# Rover_PCB_2019-02-01.net
KiCad netlist of a schematic drawn in EAGLE
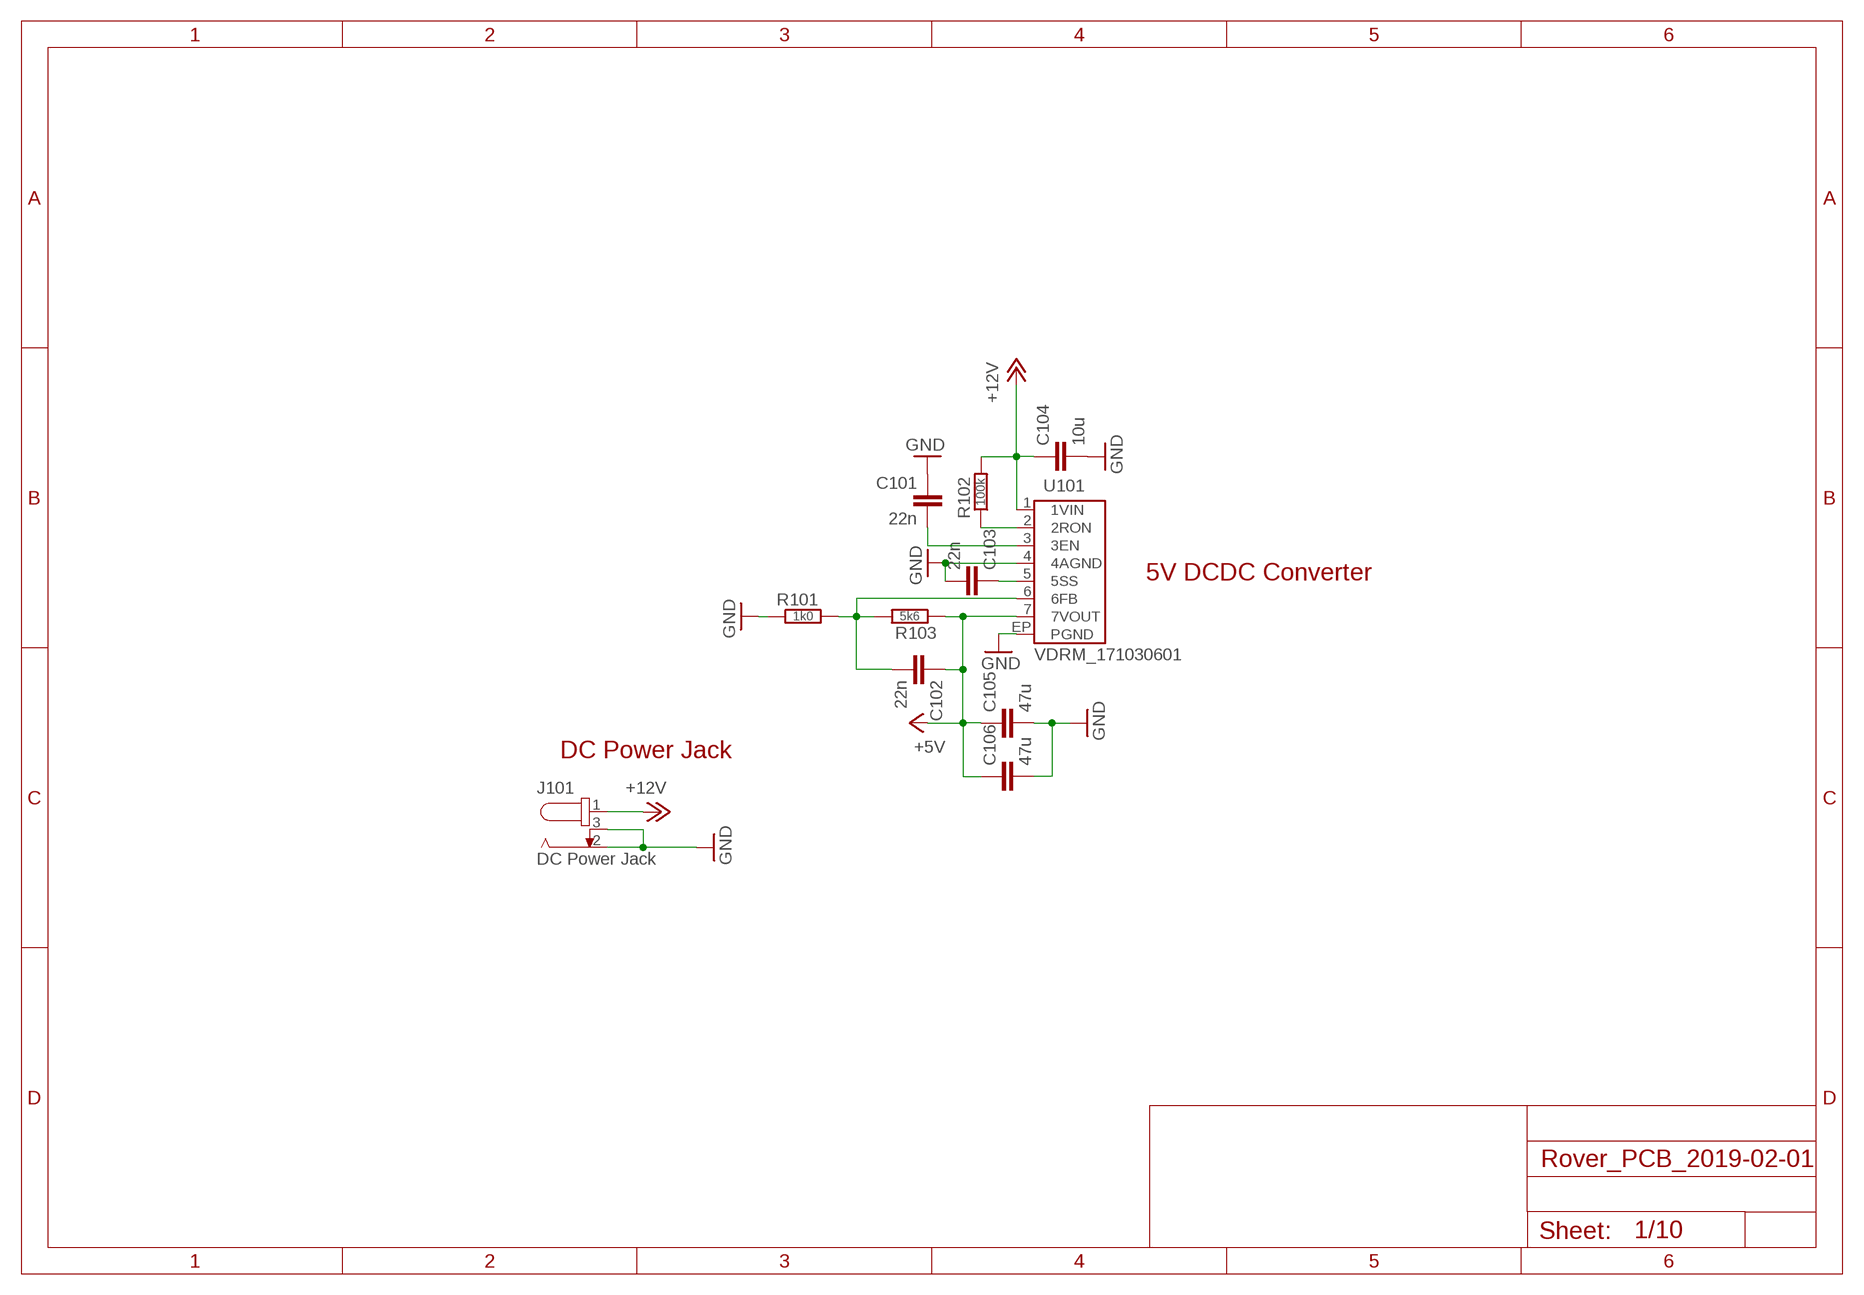
[diagram p0: schematic, sheet 1]
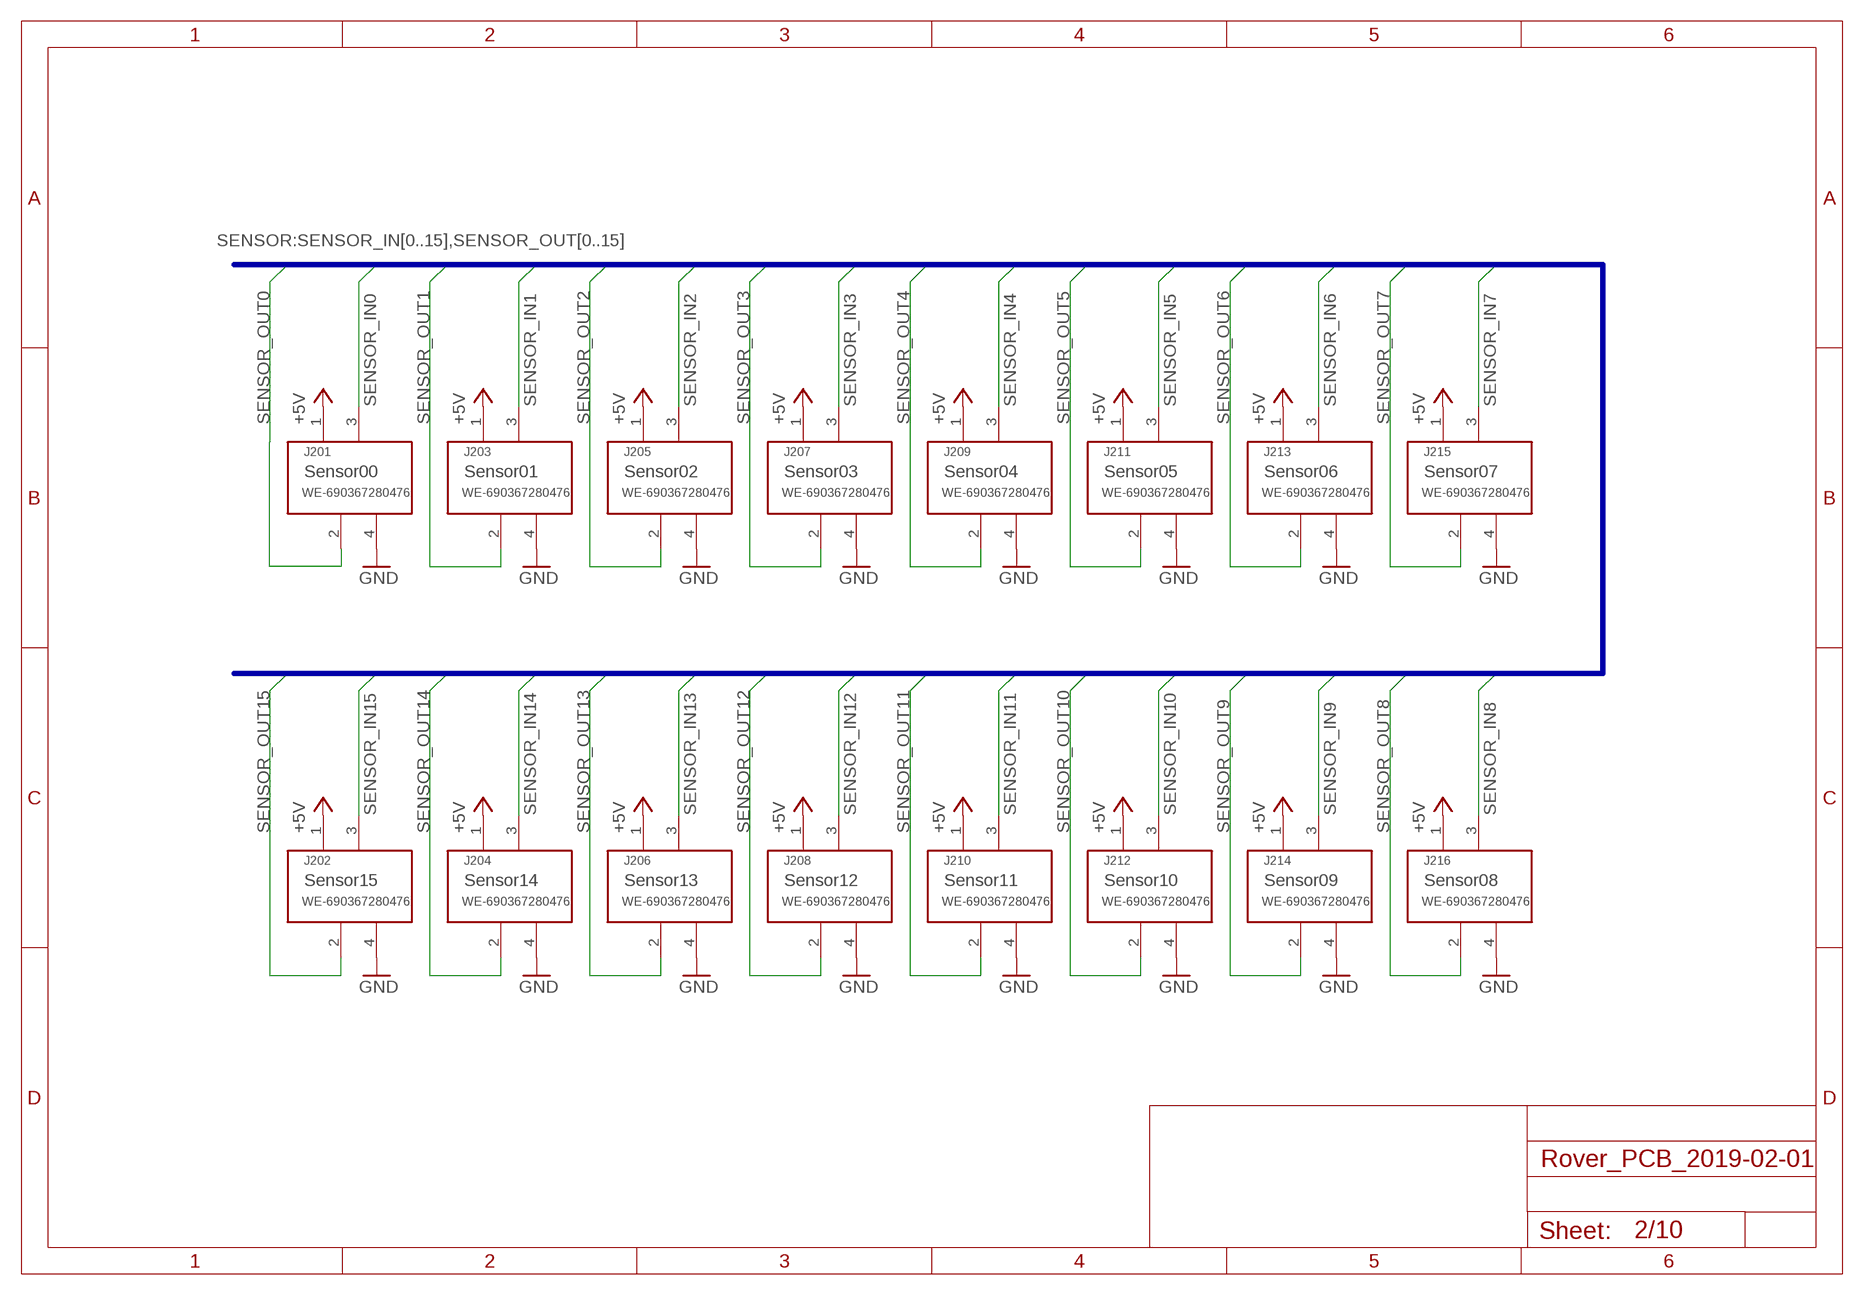
[diagram p1: schematic, sheet 2]
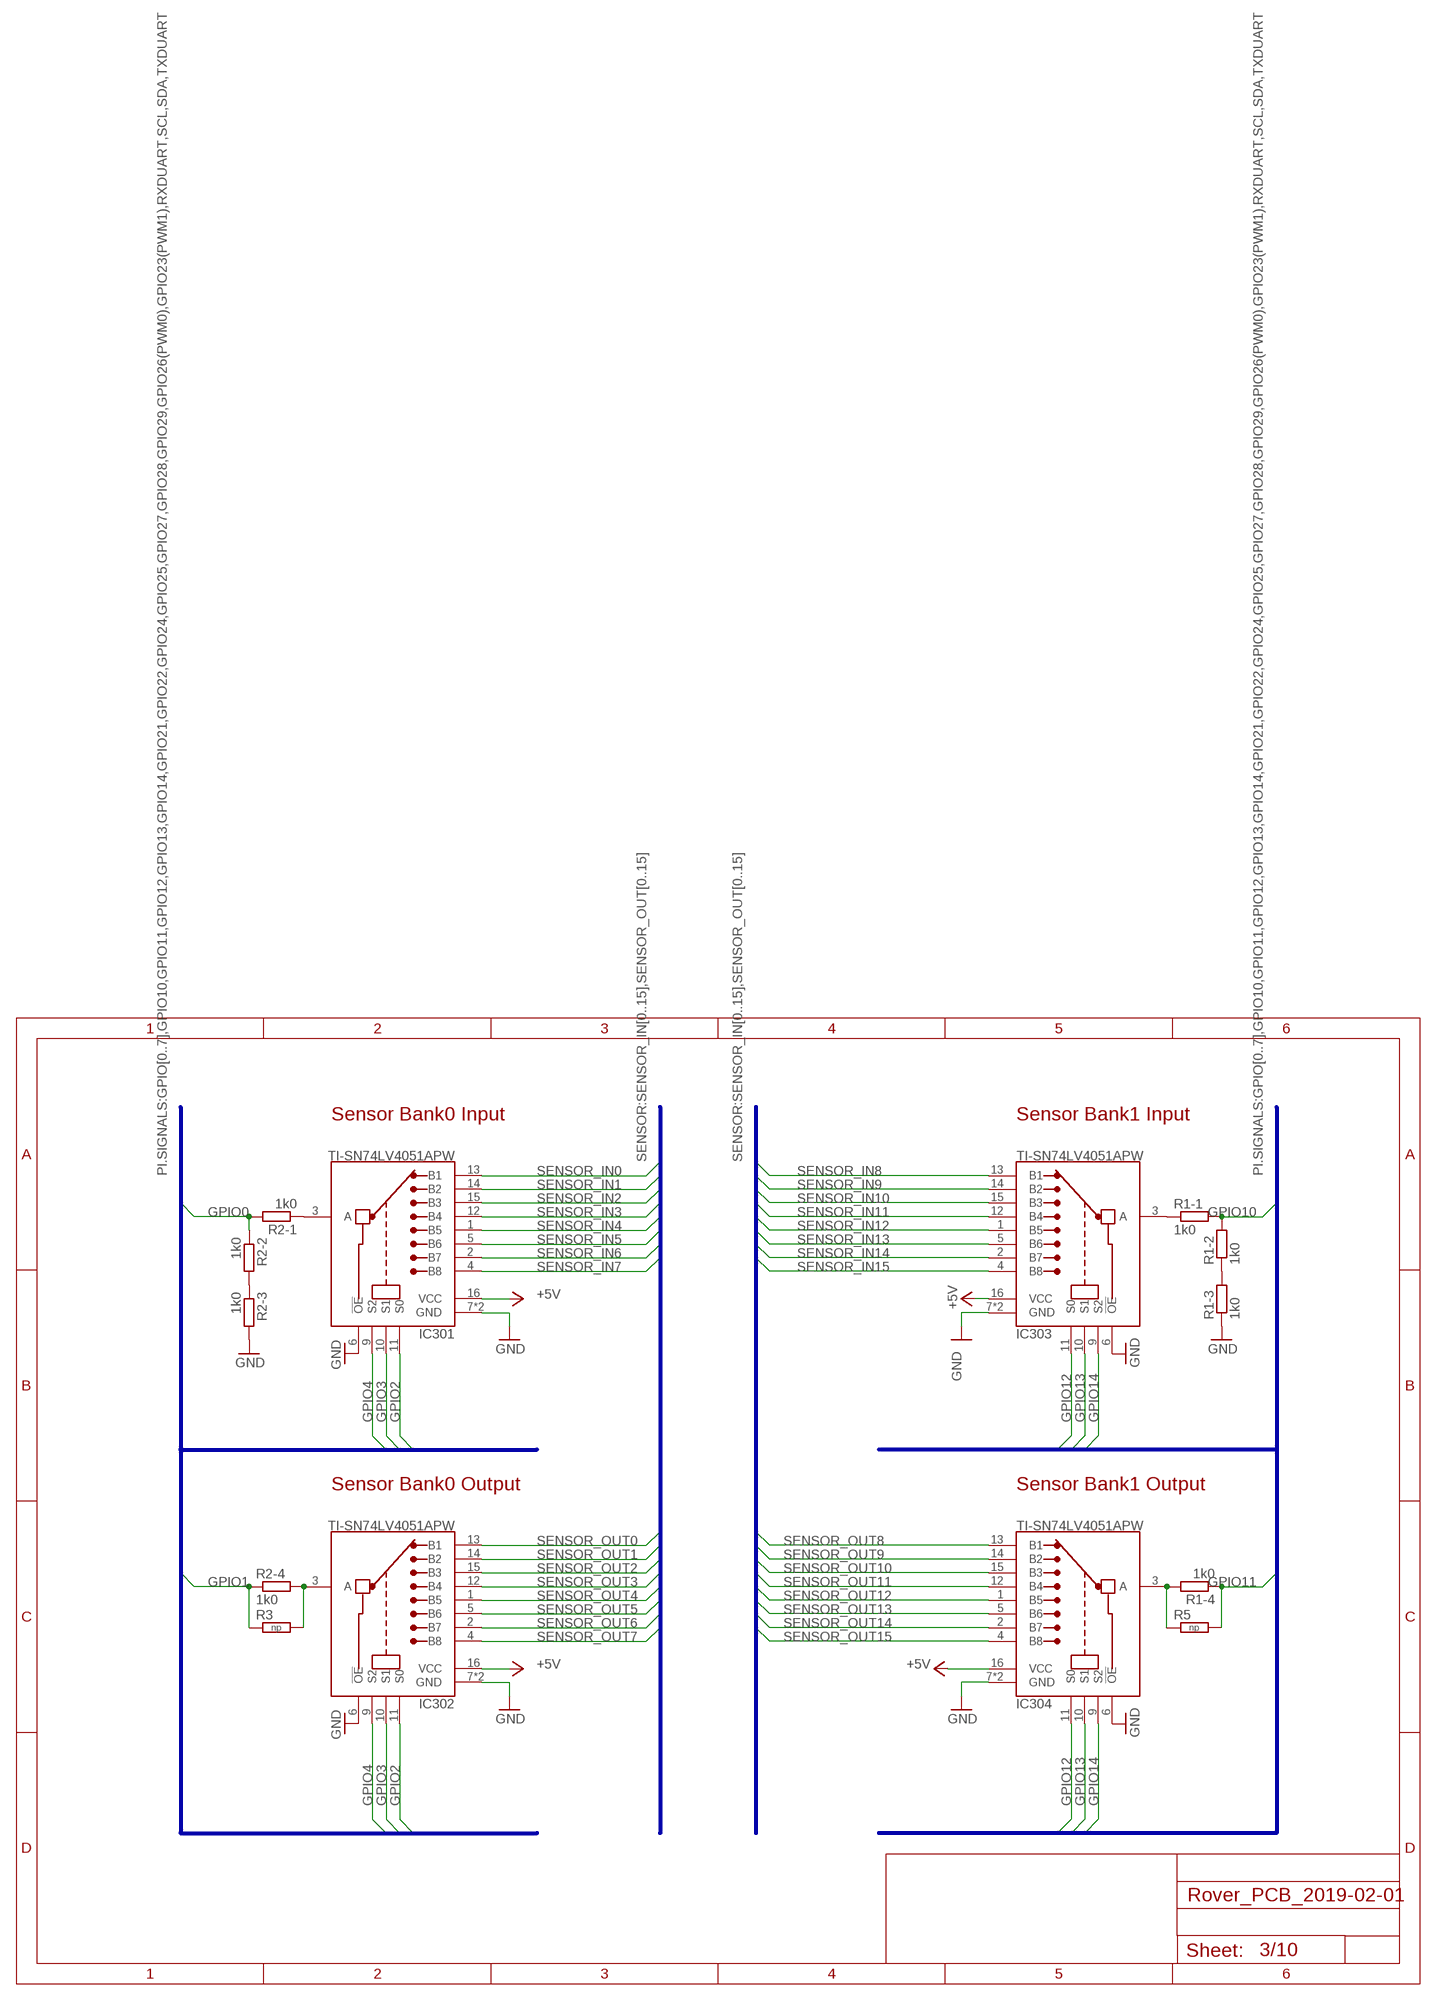
[diagram p2: schematic, sheet 3]
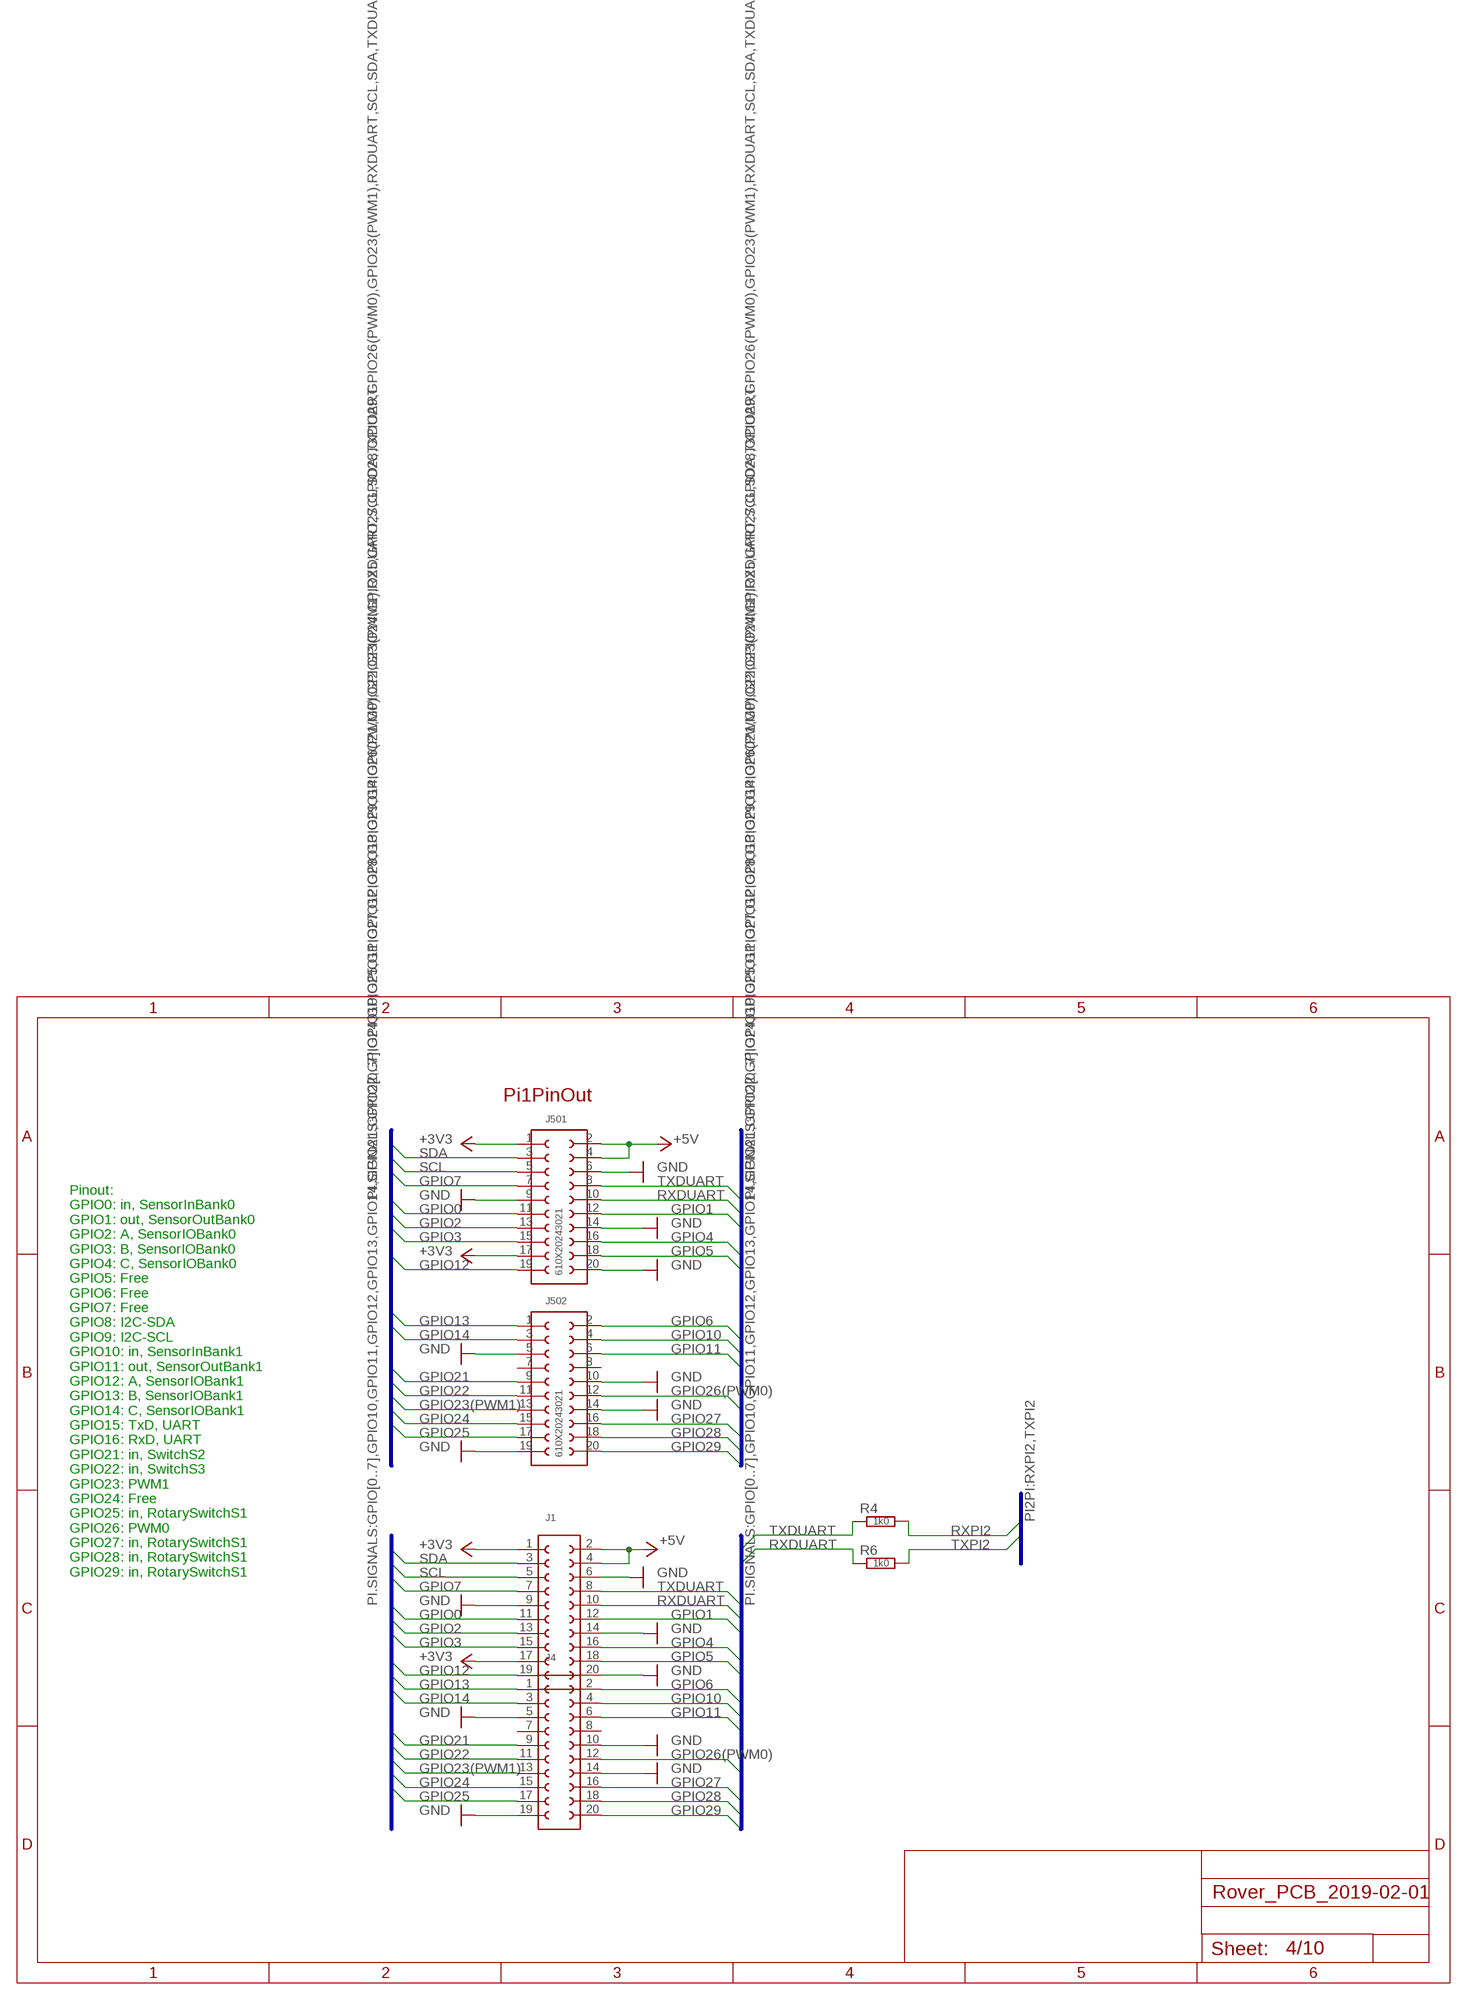
[diagram p3: schematic, sheet 4]
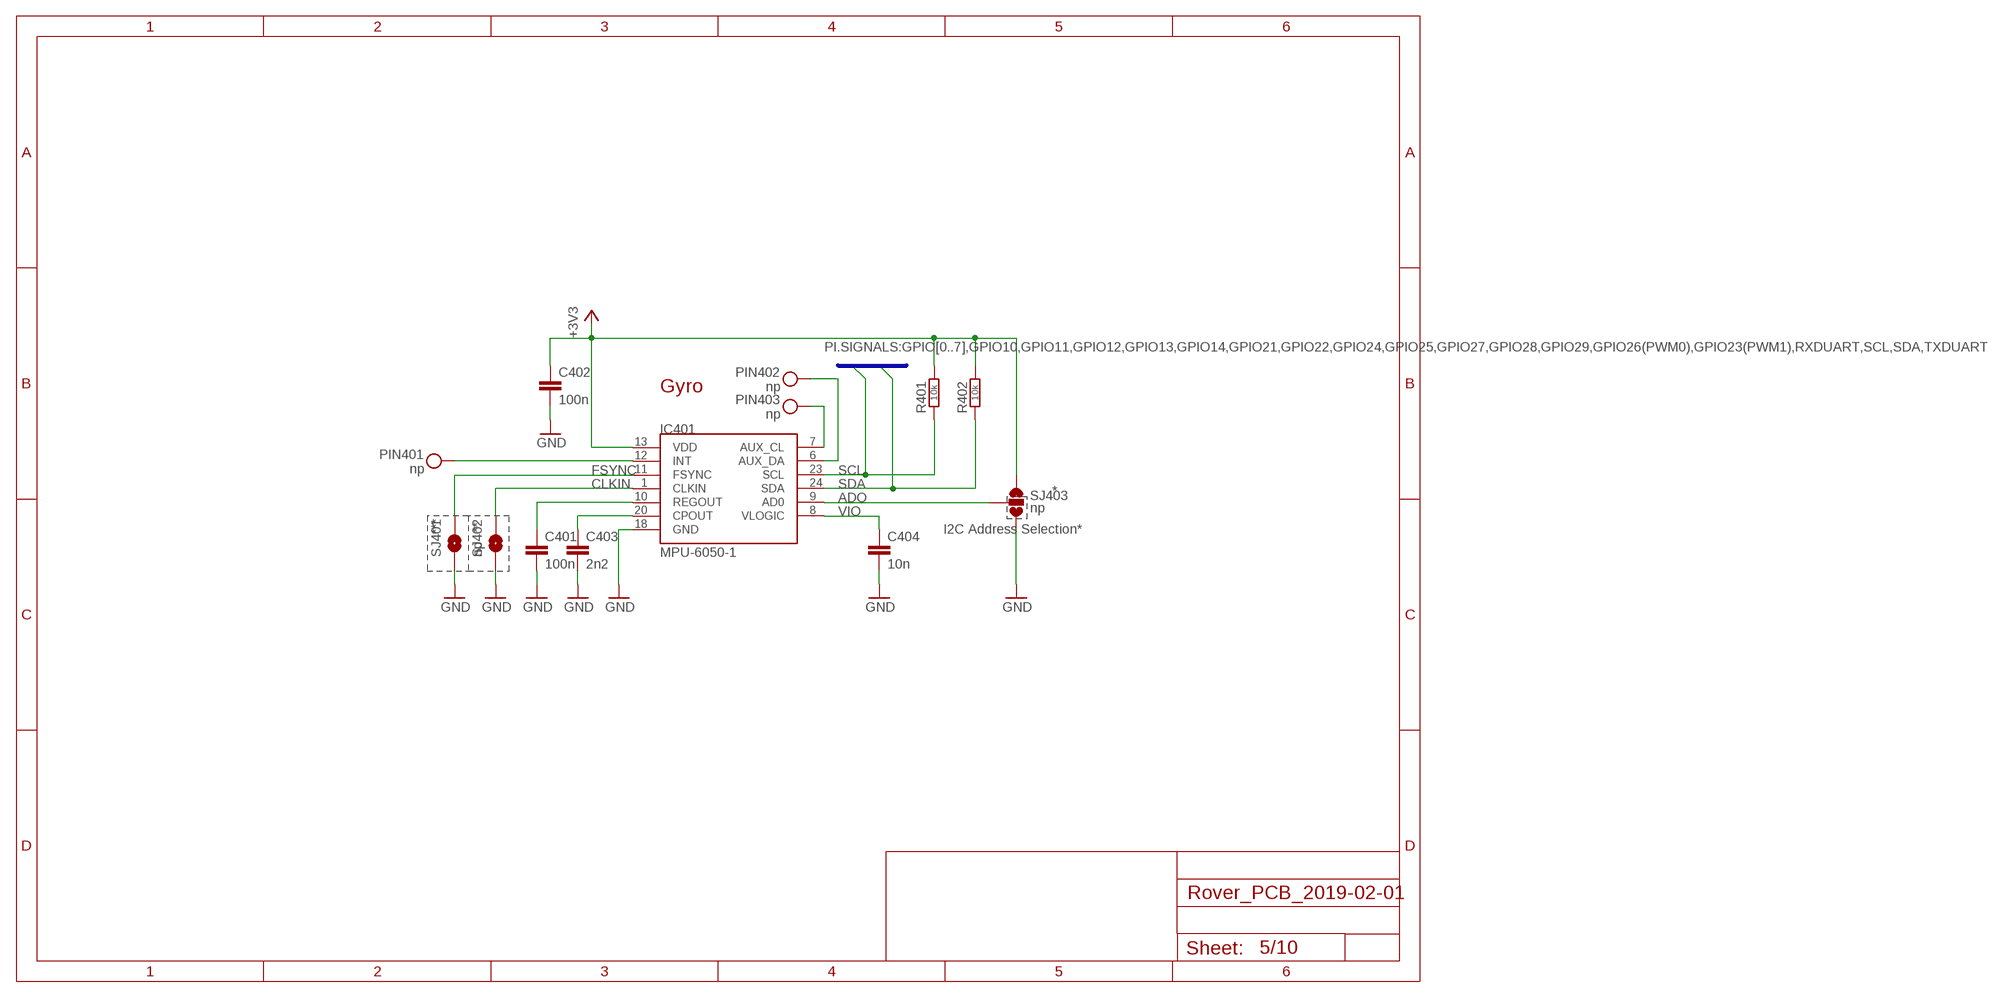
[diagram p4: schematic, sheet 5]
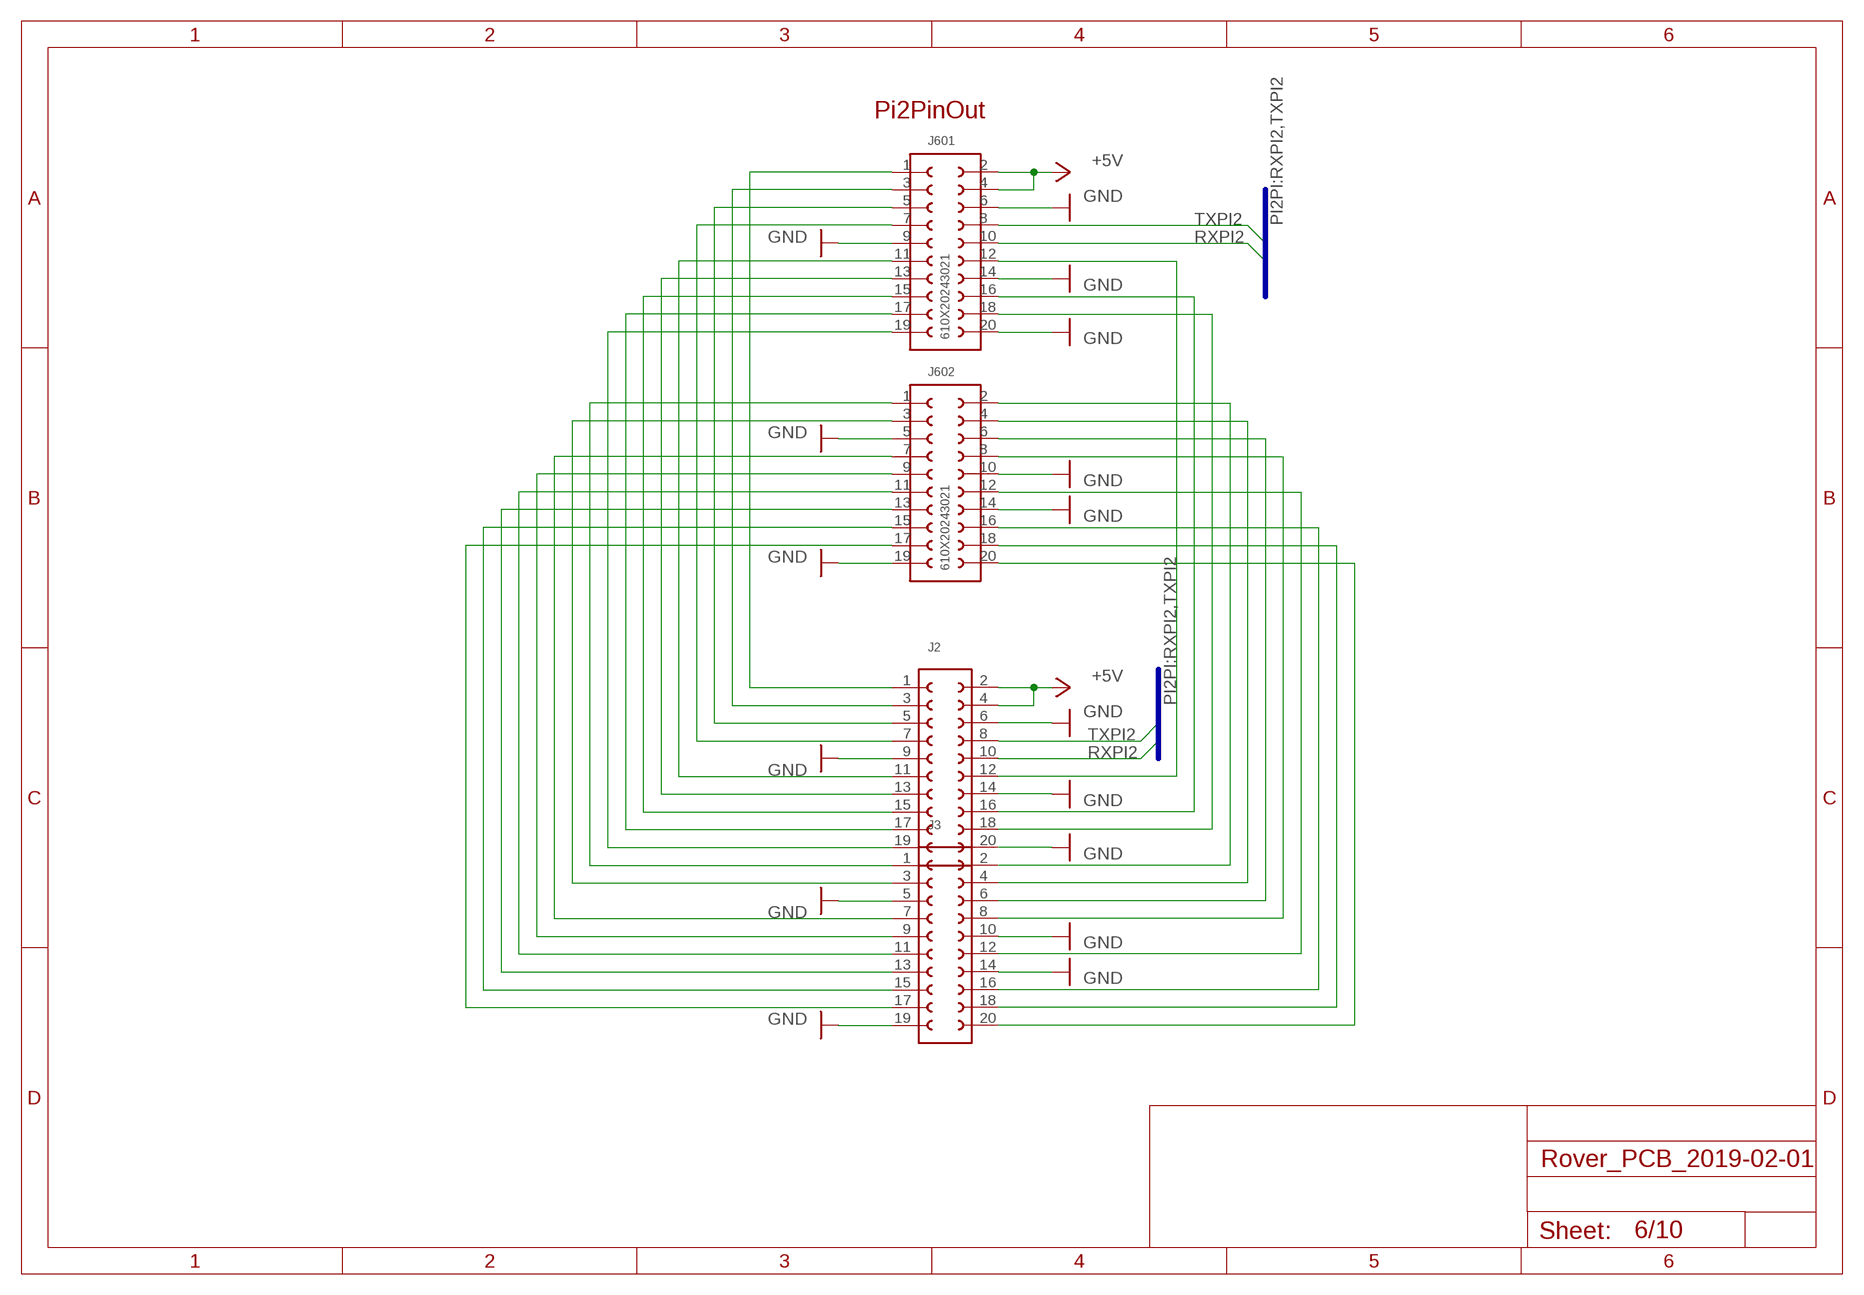
[diagram p5: schematic, sheet 6]
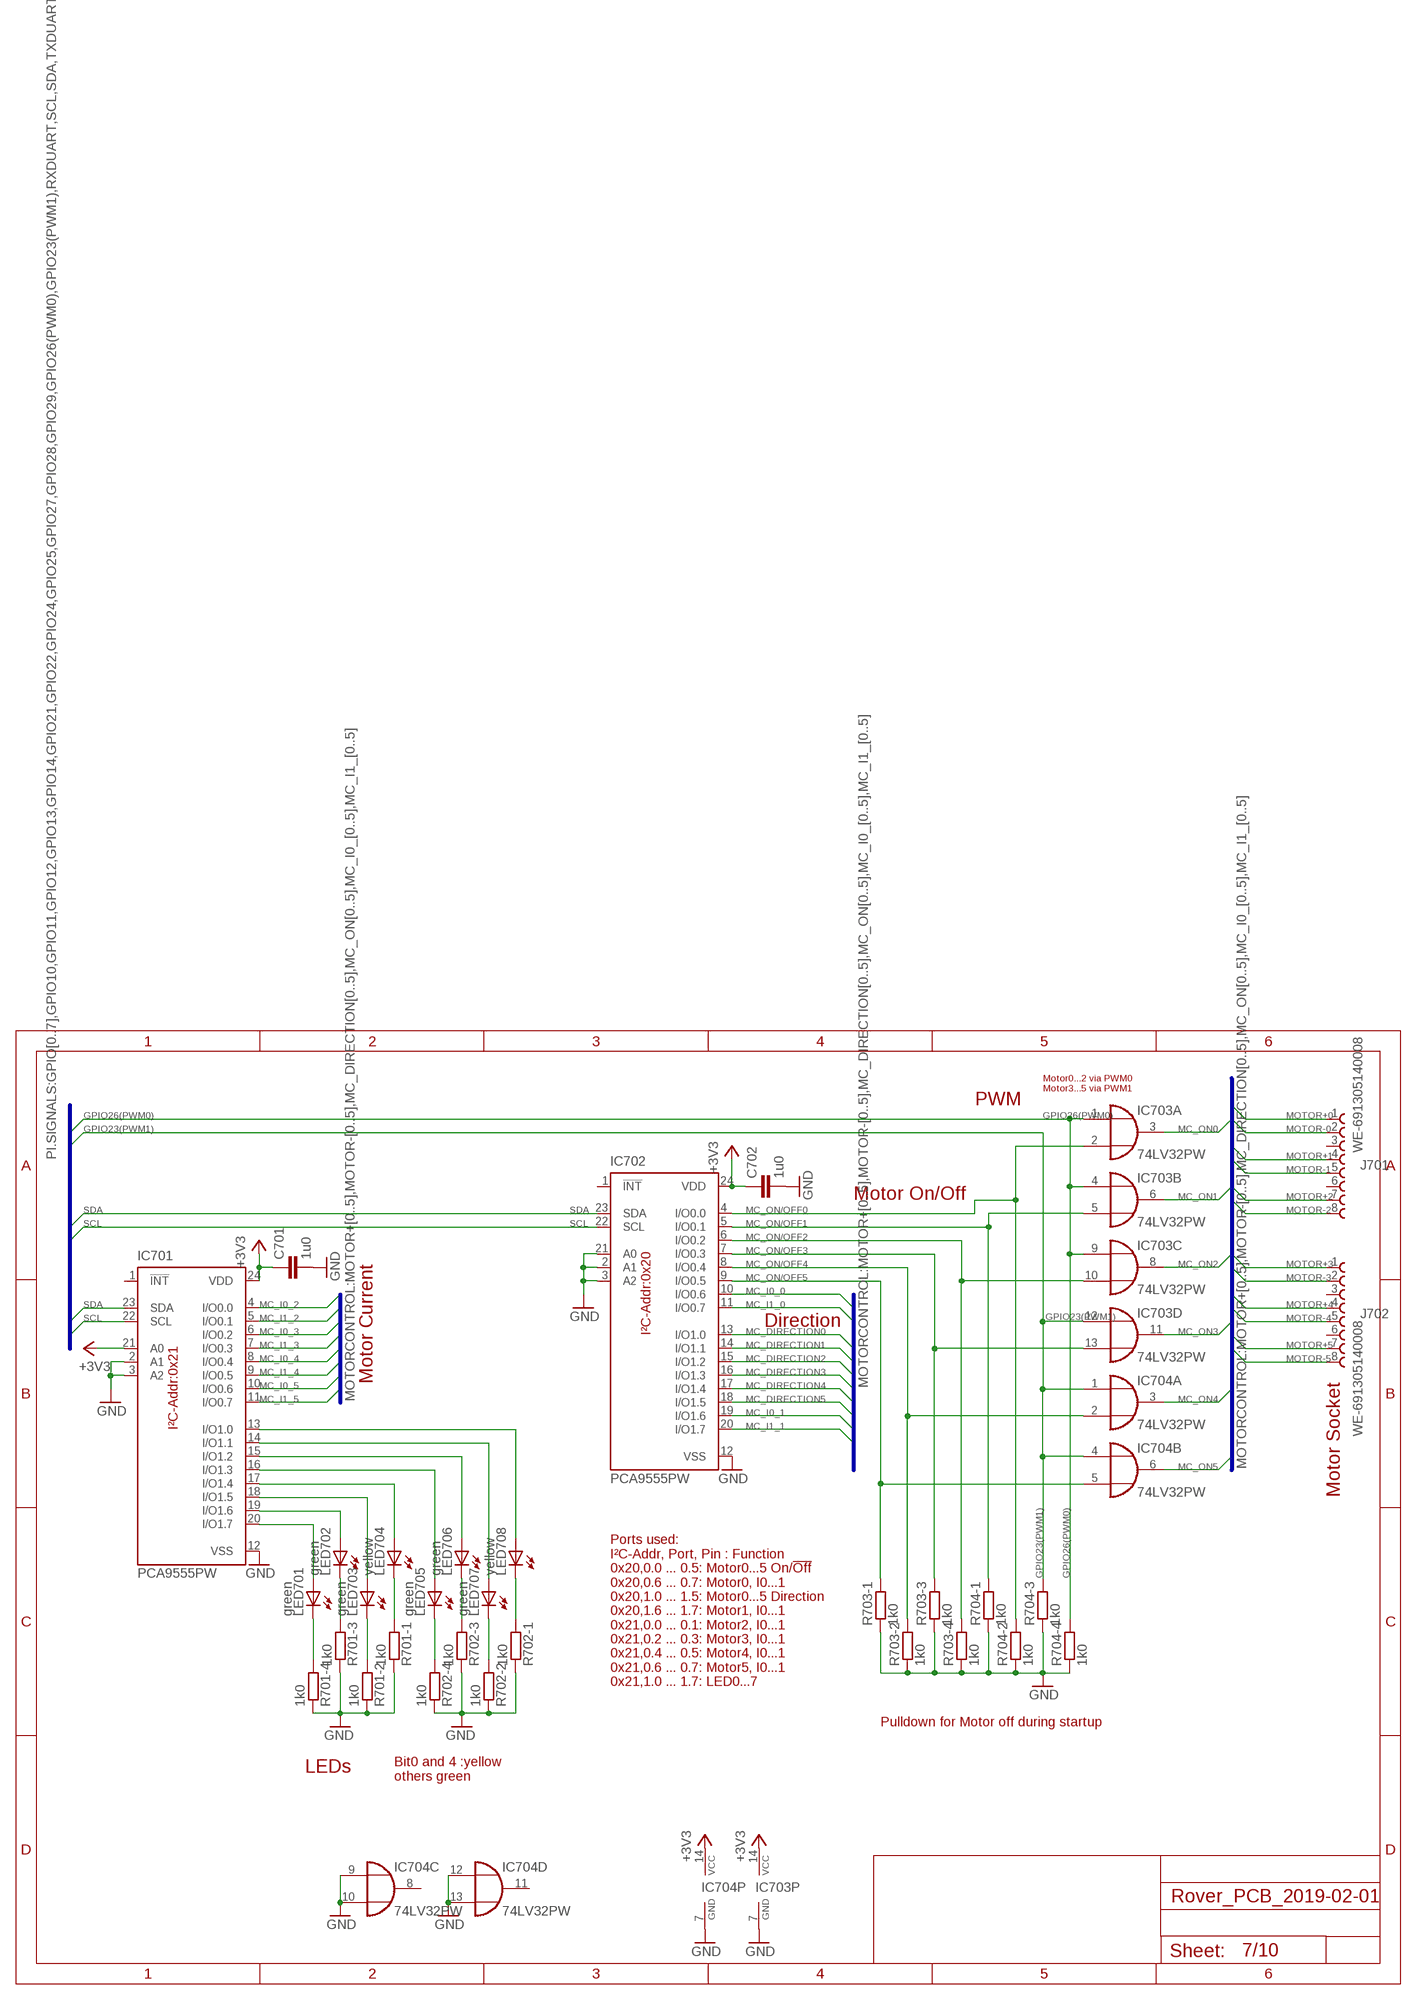
[diagram p6: schematic, sheet 7]
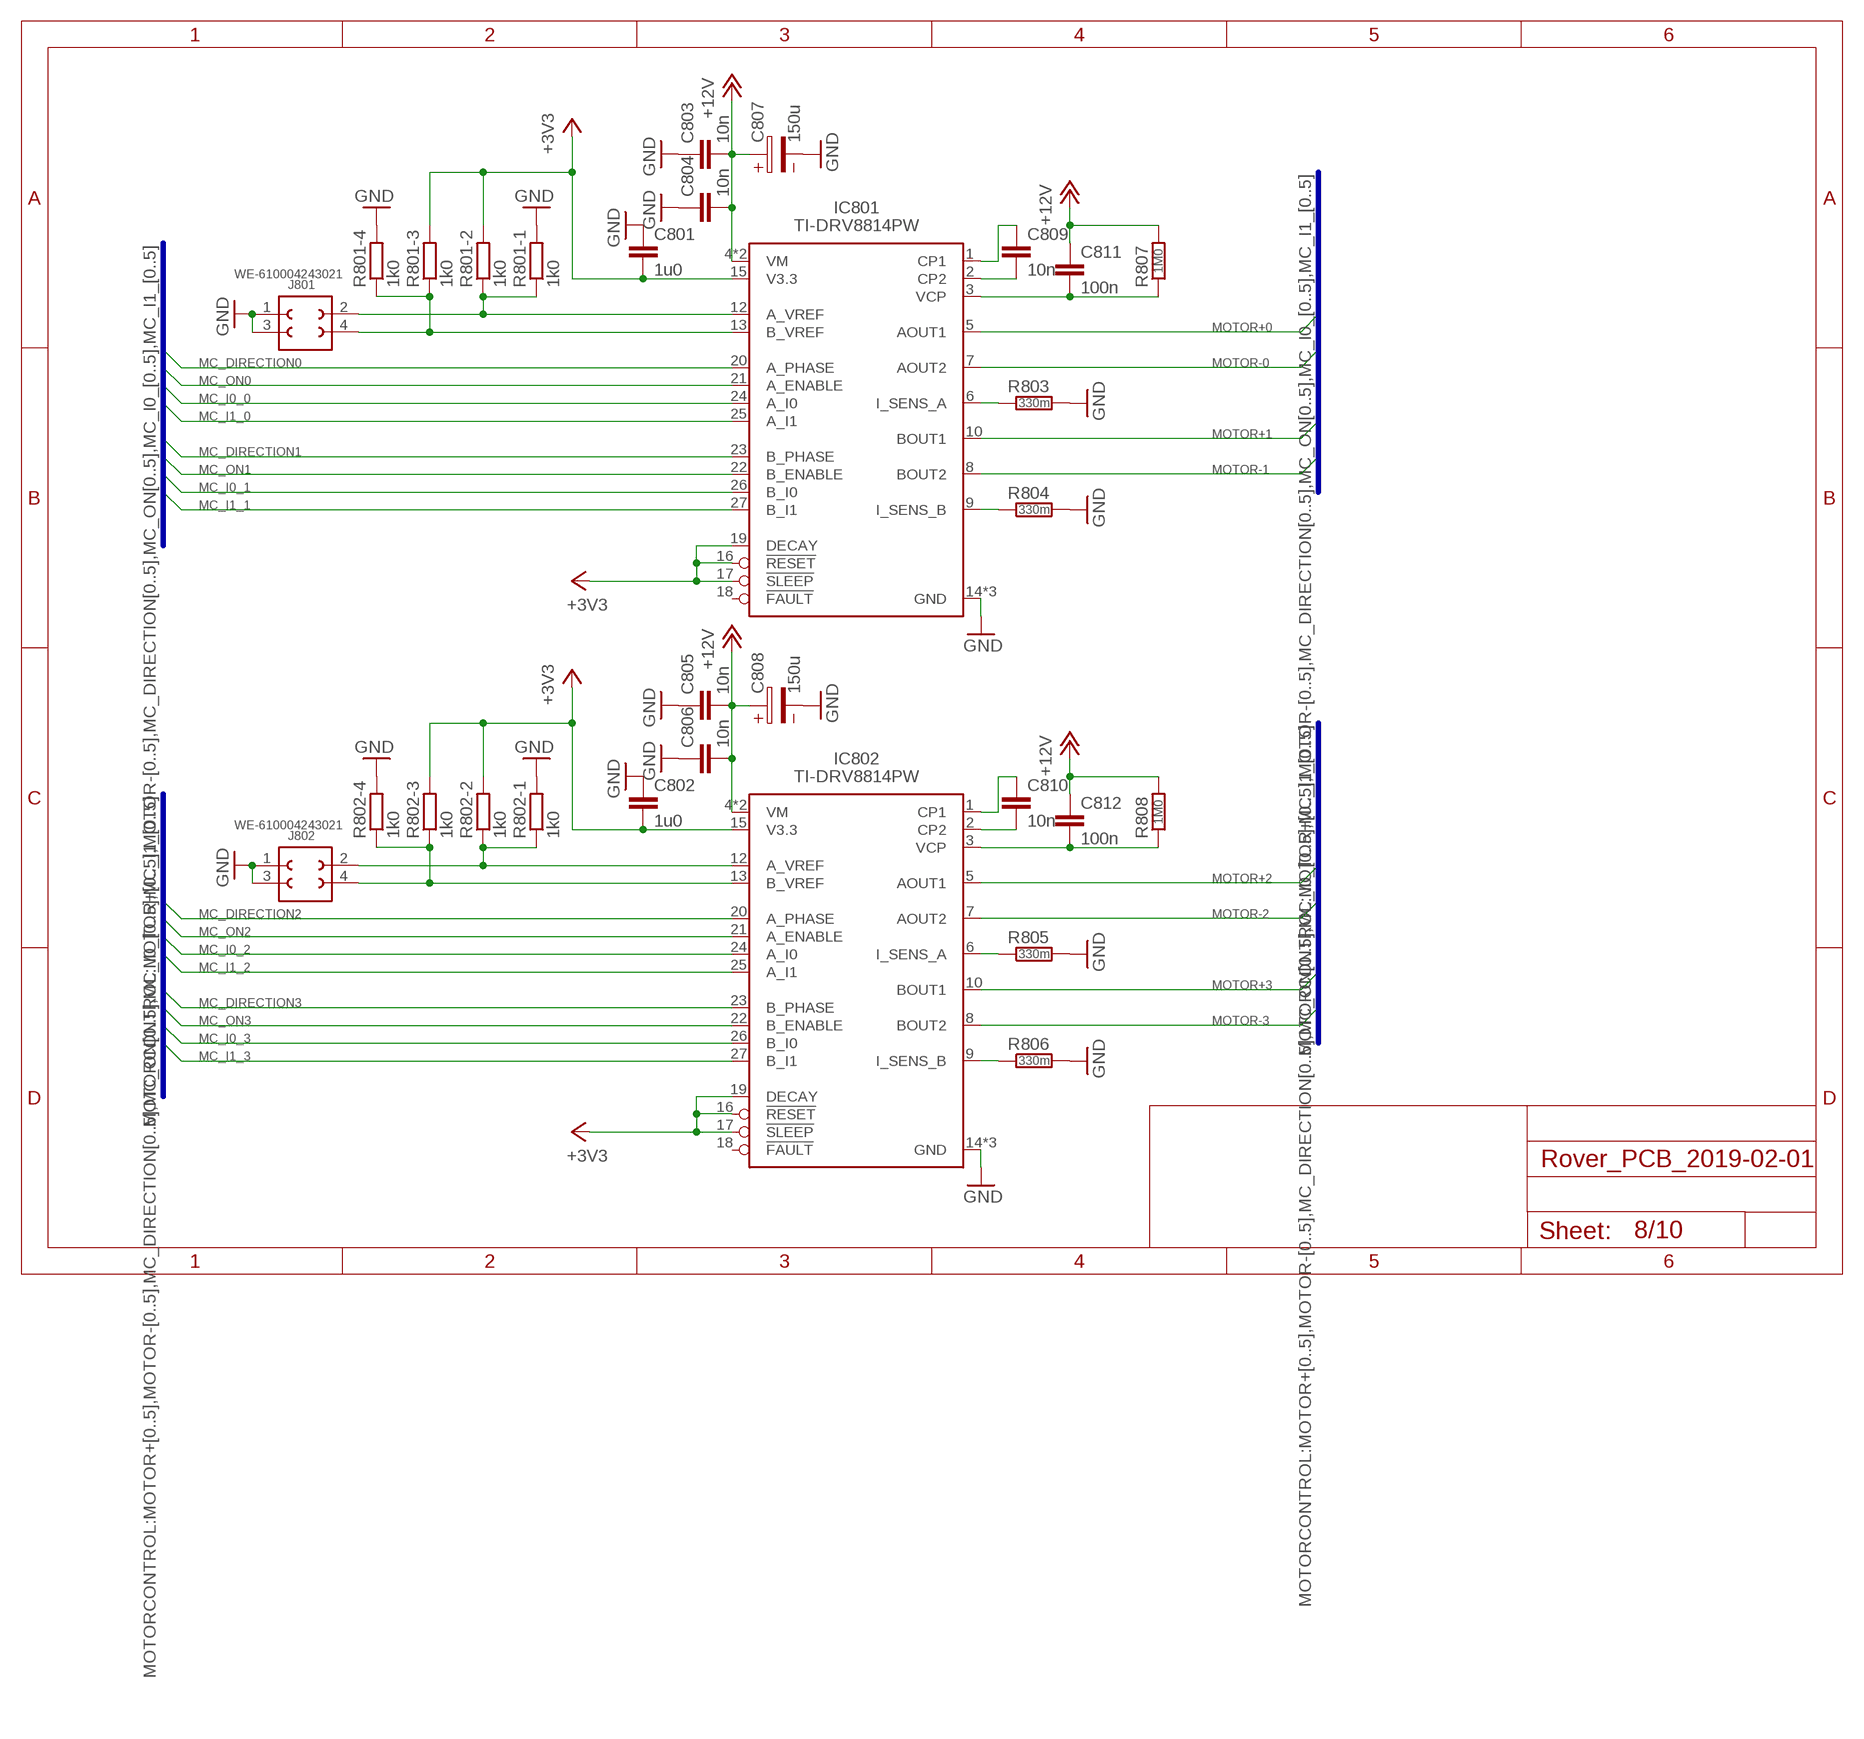
[diagram p7: schematic, sheet 8]
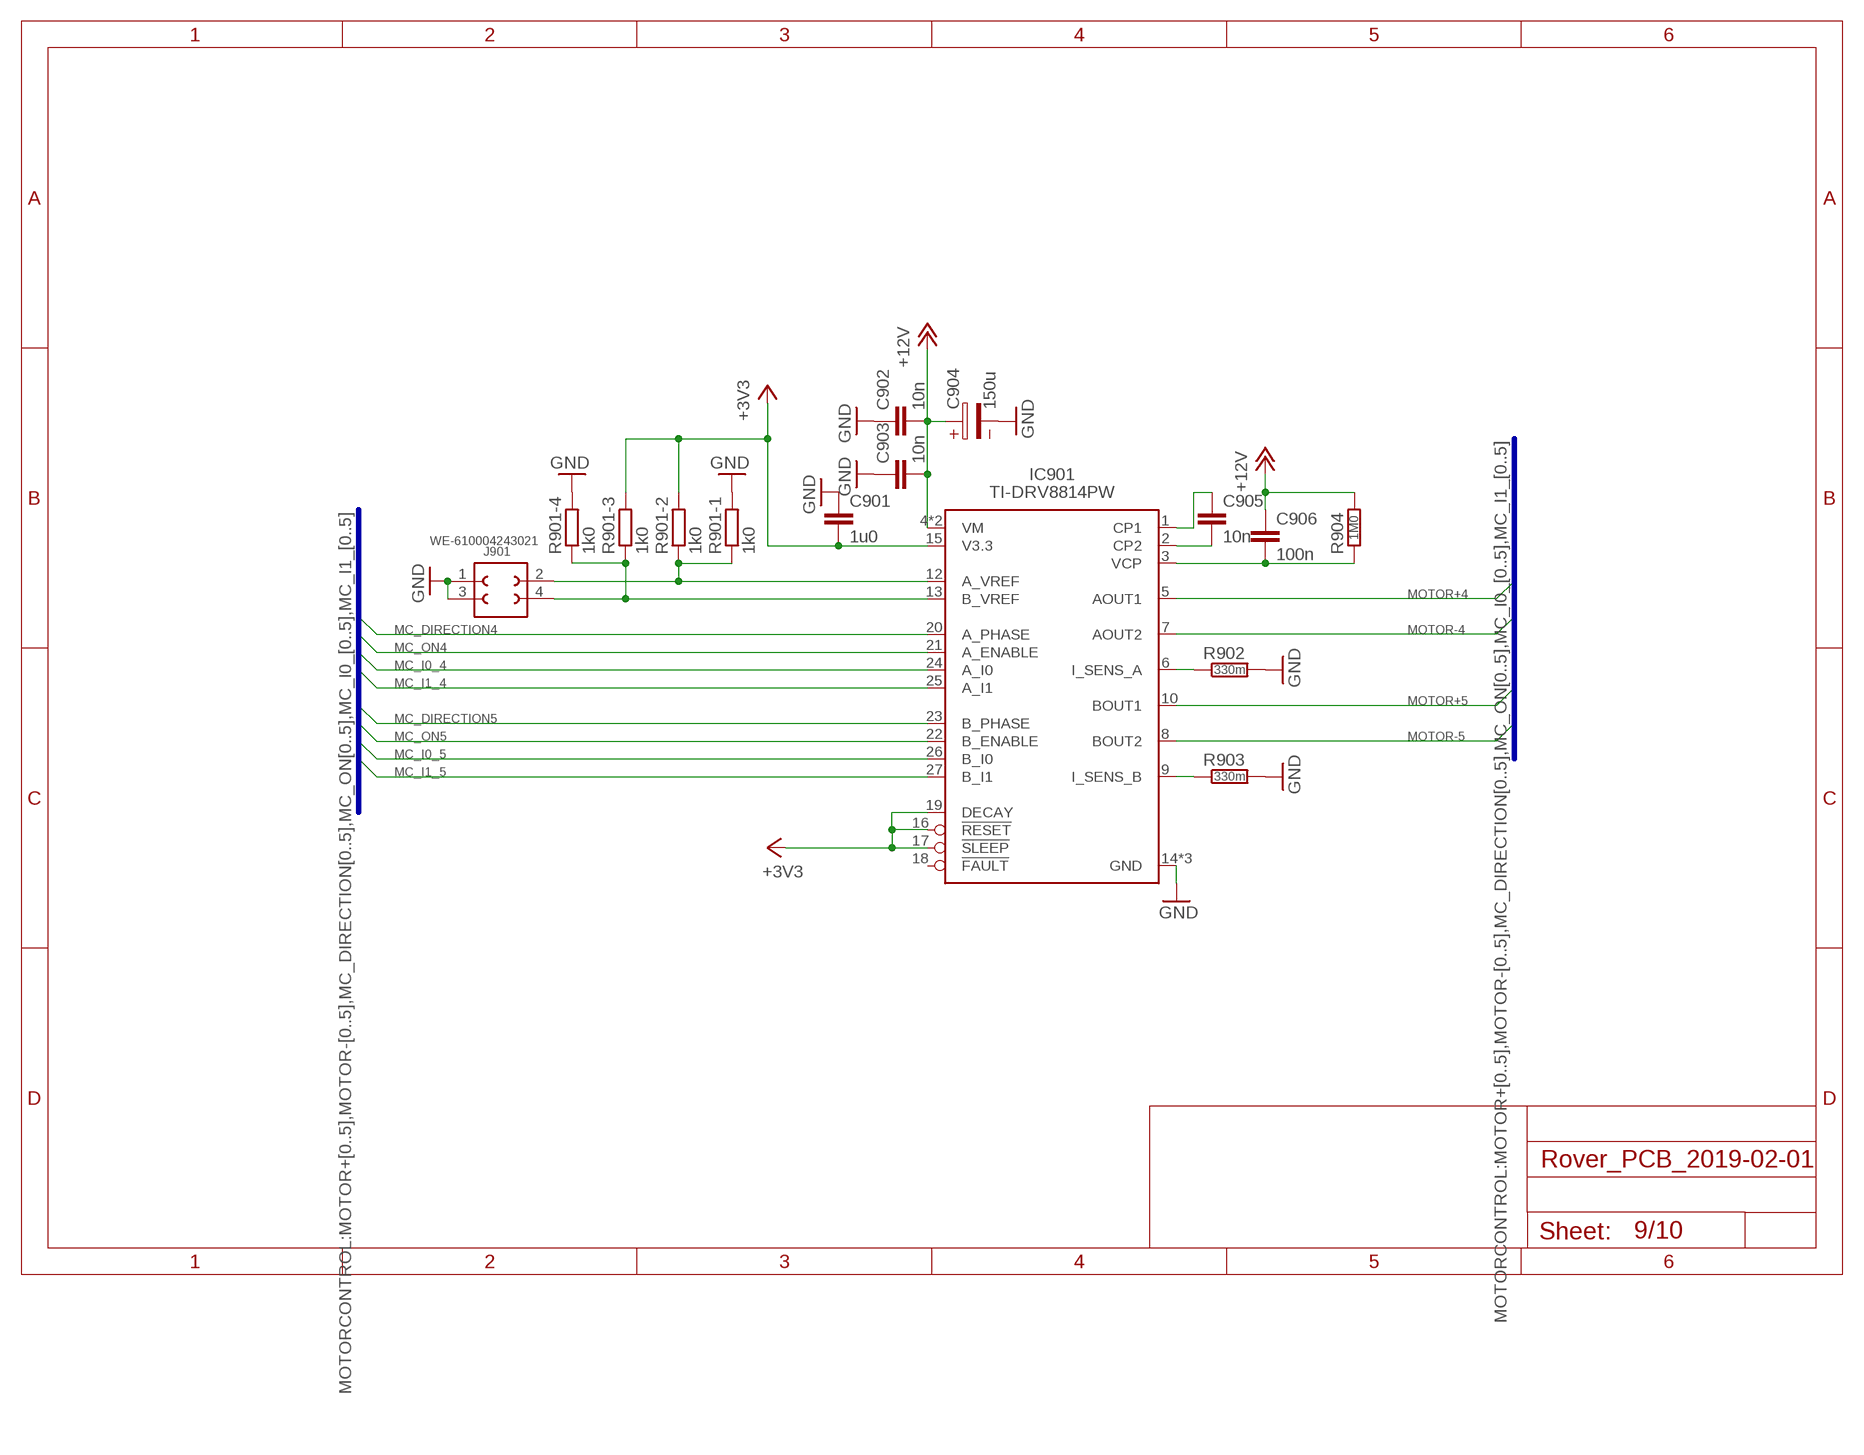
[diagram p8: schematic, sheet 9]
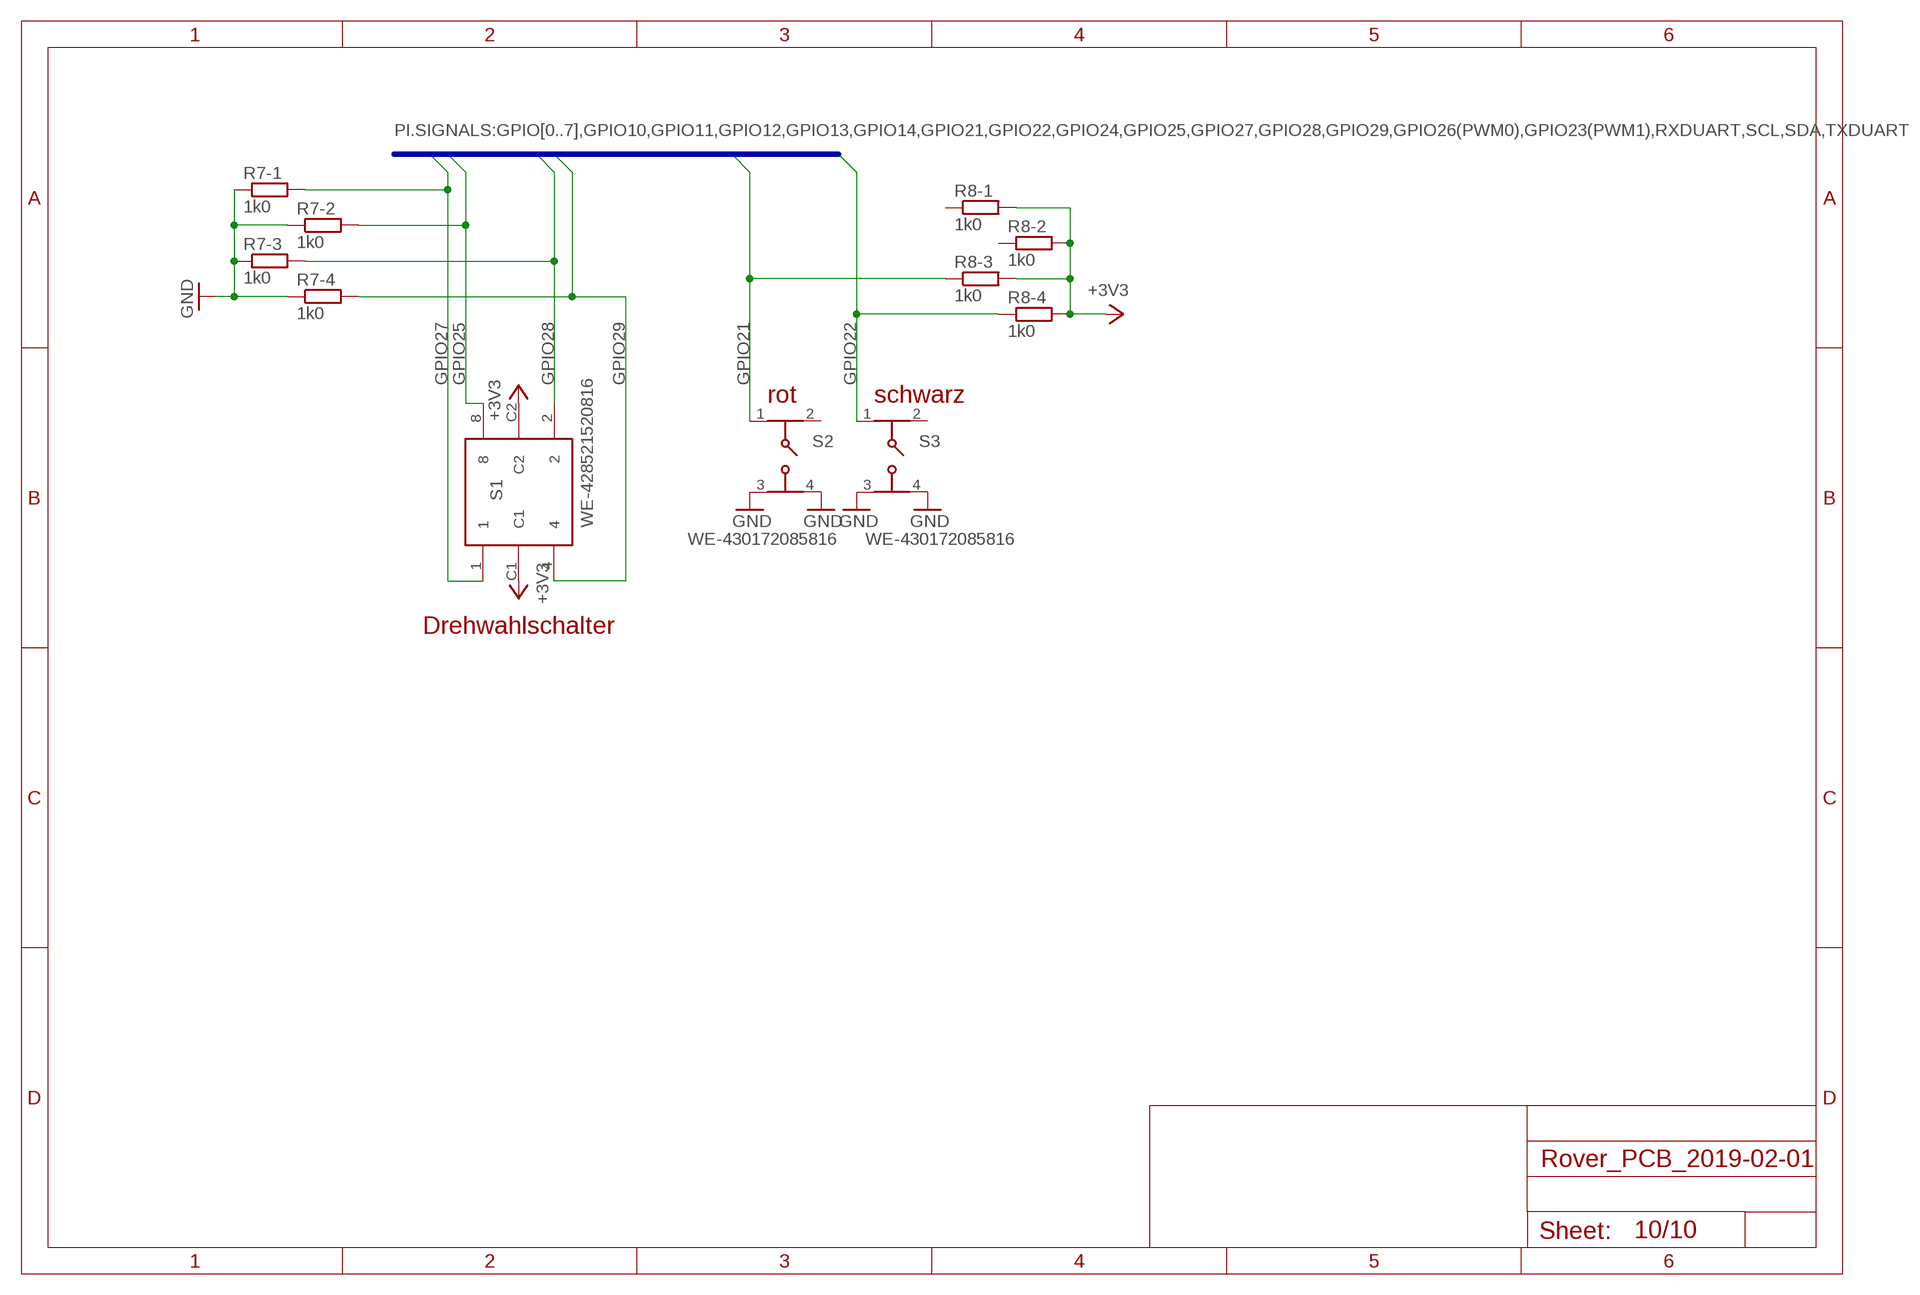
[diagram p9: schematic, sheet 10]

(export (version "E")
  (design (tool "Eeschema 10.0.6"))
  (components
    (comp (ref "J2")
      (value "610X2021121")
      (footprint "eagle-import:610X2021121")
      (libsource (lib "eagle-import") (part "610X2021121"))
    )
    (comp (ref "J3")
      (value "610X2021121")
      (footprint "eagle-import:610X2021121")
      (libsource (lib "eagle-import") (part "610X2021121"))
    )
    (comp (ref "J601")
      (value "610X20243021")
      (footprint "eagle-import:610X20243021")
      (libsource (lib "eagle-import") (part "610X20243021"))
    )
    (comp (ref "J602")
      (value "610X20243021")
      (footprint "eagle-import:610X20243021")
      (libsource (lib "eagle-import") (part "610X20243021"))
    )
    (comp (ref "IC301")
      (value "TI-SN74LV4051APW")
      (footprint "eagle-import:SOP16P65_500X640X120L62X24L")
      (libsource (lib "eagle-import") (part "TI-SN74LV4051APW"))
    )
    (comp (ref "IC302")
      (value "TI-SN74LV4051APW")
      (footprint "eagle-import:SOP16P65_500X640X120L62X24L")
      (libsource (lib "eagle-import") (part "TI-SN74LV4051APW"))
    )
    (comp (ref "IC303")
      (value "TI-SN74LV4051APW")
      (footprint "eagle-import:SOP16P65_500X640X120L62X24L")
      (libsource (lib "eagle-import") (part "TI-SN74LV4051APW"))
    )
    (comp (ref "IC304")
      (value "TI-SN74LV4051APW")
      (footprint "eagle-import:SOP16P65_500X640X120L62X24L")
      (libsource (lib "eagle-import") (part "TI-SN74LV4051APW"))
    )
    (comp (ref "R1")
      (value "1k0")
      (footprint "eagle-import:CAPCAF80P160X320X70-8L")
      (libsource (lib "eagle-import") (part "CTS-74,2C083"))
    )
    (comp (ref "R2")
      (value "1k0")
      (footprint "eagle-import:CAPCAF80P160X320X70-8L")
      (libsource (lib "eagle-import") (part "CTS-74,2C083"))
    )
    (comp (ref "R3")
      (value "np")
      (footprint "eagle-import:RESC2012X50N")
      (libsource (lib "eagle-import") (part "R-EU-R0805N"))
    )
    (comp (ref "R5")
      (value "np")
      (footprint "eagle-import:RESC2012X50N")
      (libsource (lib "eagle-import") (part "R-EU-R0805N"))
    )
    (comp (ref "J1")
      (value "610X2021121")
      (footprint "eagle-import:610X2021121")
      (libsource (lib "eagle-import") (part "610X2021121"))
    )
    (comp (ref "J4")
      (value "610X2021121")
      (footprint "eagle-import:610X2021121")
      (libsource (lib "eagle-import") (part "610X2021121"))
    )
    (comp (ref "J501")
      (value "610X20243021")
      (footprint "eagle-import:610X20243021")
      (libsource (lib "eagle-import") (part "610X20243021"))
    )
    (comp (ref "J502")
      (value "610X20243021")
      (footprint "eagle-import:610X20243021")
      (libsource (lib "eagle-import") (part "610X20243021"))
    )
    (comp (ref "R4")
      (value "1k0")
      (footprint "eagle-import:RESC2012X50N")
      (libsource (lib "eagle-import") (part "R-EU-R0805N"))
    )
    (comp (ref "R6")
      (value "1k0")
      (footprint "eagle-import:RESC2012X50N")
      (libsource (lib "eagle-import") (part "R-EU-R0805N"))
    )
    (comp (ref "R7")
      (value "1k0")
      (footprint "eagle-import:CAPCAF80P160X320X70-8L")
      (libsource (lib "eagle-import") (part "CTS-74,2C083"))
    )
    (comp (ref "R8")
      (value "1k0")
      (footprint "eagle-import:CAPCAF80P160X320X70-8L")
      (libsource (lib "eagle-import") (part "CTS-74,2C083"))
    )
    (comp (ref "S1")
      (value "WE-428521520816")
      (footprint "eagle-import:428521520816")
      (libsource (lib "eagle-import") (part "428521520816"))
    )
    (comp (ref "S2")
      (value "WE-430172085816")
      (footprint "eagle-import:4301X20438X6")
      (libsource (lib "eagle-import") (part "430162043826"))
    )
    (comp (ref "S3")
      (value "WE-430172085816")
      (footprint "eagle-import:4301X20438X6")
      (libsource (lib "eagle-import") (part "430162043826"))
    )
    (comp (ref "C901")
      (value "1u0")
      (footprint "eagle-import:CAPC2012X95N")
      (libsource (lib "eagle-import") (part "C-EUC0805N"))
    )
    (comp (ref "C902")
      (value "10n")
      (footprint "eagle-import:CAPC2012X95N")
      (libsource (lib "eagle-import") (part "C-EUC0805N"))
    )
    (comp (ref "C903")
      (value "10n")
      (footprint "eagle-import:CAPC2012X95N")
      (libsource (lib "eagle-import") (part "C-EUC0805N"))
    )
    (comp (ref "C904")
      (value "150u")
      (footprint "eagle-import:4.2X1.9X2.8(BXCXA)")
      (libsource (lib "eagle-import") (part "WCAP-PSHP_875115452004_8X8,7"))
    )
    (comp (ref "C905")
      (value "10n")
      (footprint "eagle-import:CAPC2012X95N")
      (libsource (lib "eagle-import") (part "C-EUC0805N"))
    )
    (comp (ref "C906")
      (value "100n")
      (footprint "eagle-import:CAPC2012X95N")
      (libsource (lib "eagle-import") (part "C-EUC0805N"))
    )
    (comp (ref "IC901")
      (value "TI-DRV8814PW")
      (footprint "eagle-import:SOP29P65_970X640X120L60X24T500X270N")
      (libsource (lib "eagle-import") (part "TI-DRV8814PW"))
    )
    (comp (ref "J901")
      (value "WE-610004243021")
      (footprint "eagle-import:610X04243021")
      (libsource (lib "eagle-import") (part "610X04243021"))
    )
    (comp (ref "R901")
      (value "1k0")
      (footprint "eagle-import:CAPCAF80P160X320X70-8L")
      (libsource (lib "eagle-import") (part "CTS-74,2C083"))
    )
    (comp (ref "R902")
      (value "330m")
      (footprint "eagle-import:RESC160X320X65L50L")
      (libsource (lib "eagle-import") (part "R-EU-R0612L"))
    )
    (comp (ref "R903")
      (value "330m")
      (footprint "eagle-import:RESC160X320X65L50L")
      (libsource (lib "eagle-import") (part "R-EU-R0612L"))
    )
    (comp (ref "R904")
      (value "1M0")
      (footprint "eagle-import:RESC2012X50N")
      (libsource (lib "eagle-import") (part "R-EU-R0805N"))
    )
    (comp (ref "C101")
      (value "22n")
      (footprint "eagle-import:CAPC2012X95N")
      (libsource (lib "eagle-import") (part "C-EUC0805N"))
    )
    (comp (ref "C102")
      (value "22n")
      (footprint "eagle-import:CAPC2012X95N")
      (libsource (lib "eagle-import") (part "C-EUC0805N"))
    )
    (comp (ref "C103")
      (value "22n")
      (footprint "eagle-import:CAPC2012X95N")
      (libsource (lib "eagle-import") (part "C-EUC0805N"))
    )
    (comp (ref "C104")
      (value "10u")
      (footprint "eagle-import:CAP-US1210-EU3225")
      (libsource (lib "eagle-import") (part "C-EUC1210N"))
    )
    (comp (ref "C105")
      (value "47u")
      (footprint "eagle-import:CAP-US1210-EU3225")
      (libsource (lib "eagle-import") (part "C-EUC1210N"))
    )
    (comp (ref "C106")
      (value "47u")
      (footprint "eagle-import:CAP-US1210-EU3225")
      (libsource (lib "eagle-import") (part "C-EUC1210N"))
    )
    (comp (ref "J101")
      (value "DC Power Jack")
      (footprint "eagle-import:69410X105102")
      (libsource (lib "eagle-import") (part "694108105102"))
    )
    (comp (ref "R101")
      (value "1k0")
      (footprint "eagle-import:RESC2012X50N")
      (libsource (lib "eagle-import") (part "R-EU-R0805N"))
    )
    (comp (ref "R102")
      (value "100k")
      (footprint "eagle-import:RESC2012X50N")
      (libsource (lib "eagle-import") (part "R-EU-R0805N"))
    )
    (comp (ref "R103")
      (value "5k6")
      (footprint "eagle-import:RESC2012X50N")
      (libsource (lib "eagle-import") (part "R-EU-R0805N"))
    )
    (comp (ref "U101")
      (value "VDRM_171030601")
      (footprint "eagle-import:VDRM_7PIN-PFM")
      (libsource (lib "eagle-import") (part "VDRM_171030601"))
    )
    (comp (ref "C401")
      (value "100n")
      (footprint "eagle-import:CAPC2012X95N")
      (libsource (lib "eagle-import") (part "C-EUC0805N"))
    )
    (comp (ref "C402")
      (value "100n")
      (footprint "eagle-import:CAPC2012X95N")
      (libsource (lib "eagle-import") (part "C-EUC0805N"))
    )
    (comp (ref "C403")
      (value "2n2")
      (footprint "eagle-import:CAPC2012X95N")
      (libsource (lib "eagle-import") (part "C-EUC0805N"))
    )
    (comp (ref "C404")
      (value "10n")
      (footprint "eagle-import:CAPC2012X95N")
      (libsource (lib "eagle-import") (part "C-EUC0805N"))
    )
    (comp (ref "IC401")
      (value "MPU-6050-1")
      (footprint "eagle-import:QFN-24-4MM2")
      (libsource (lib "eagle-import") (part "MPU-6050-1"))
    )
    (comp (ref "PIN401")
      (value "np")
      (footprint "eagle-import:SOLDER_PIN_0.5")
      (libsource (lib "eagle-import") (part "SOLDER_PIN-0.5"))
    )
    (comp (ref "PIN402")
      (value "np")
      (footprint "eagle-import:SOLDER_PIN_0.5")
      (libsource (lib "eagle-import") (part "SOLDER_PIN-0.5"))
    )
    (comp (ref "PIN403")
      (value "np")
      (footprint "eagle-import:SOLDER_PIN_0.5")
      (libsource (lib "eagle-import") (part "SOLDER_PIN-0.5"))
    )
    (comp (ref "R401")
      (value "10k")
      (footprint "eagle-import:RESC2012X50N")
      (libsource (lib "eagle-import") (part "R-EU-R0805N"))
    )
    (comp (ref "R402")
      (value "10k")
      (footprint "eagle-import:RESC2012X50N")
      (libsource (lib "eagle-import") (part "R-EU-R0805N"))
    )
    (comp (ref "SJ401")
      (value "np")
      (footprint "eagle-import:SJ_2S-TRACE")
      (libsource (lib "eagle-import") (part "SparkFun_SOLDERJUMPERTRACE"))
    )
    (comp (ref "SJ402")
      (value "np")
      (footprint "eagle-import:SJ_2S-TRACE")
      (libsource (lib "eagle-import") (part "SOLDERJUMPERTRACE"))
    )
    (comp (ref "SJ403")
      (value "np")
      (footprint "eagle-import:SJ_3_PASTE1&2")
      (libsource (lib "eagle-import") (part "SOLDERJUMPER_2WAYPASTE1&2"))
    )
    (comp (ref "C801")
      (value "1u0")
      (footprint "eagle-import:CAPC2012X95N")
      (libsource (lib "eagle-import") (part "C-EUC0805N"))
    )
    (comp (ref "C802")
      (value "1u0")
      (footprint "eagle-import:CAPC2012X95N")
      (libsource (lib "eagle-import") (part "C-EUC0805N"))
    )
    (comp (ref "C803")
      (value "10n")
      (footprint "eagle-import:CAPC2012X95N")
      (libsource (lib "eagle-import") (part "C-EUC0805N"))
    )
    (comp (ref "C804")
      (value "10n")
      (footprint "eagle-import:CAPC2012X95N")
      (libsource (lib "eagle-import") (part "C-EUC0805N"))
    )
    (comp (ref "C805")
      (value "10n")
      (footprint "eagle-import:CAPC2012X95N")
      (libsource (lib "eagle-import") (part "C-EUC0805N"))
    )
    (comp (ref "C806")
      (value "10n")
      (footprint "eagle-import:CAPC2012X95N")
      (libsource (lib "eagle-import") (part "C-EUC0805N"))
    )
    (comp (ref "C807")
      (value "150u")
      (footprint "eagle-import:4.2X1.9X2.8(BXCXA)")
      (libsource (lib "eagle-import") (part "WCAP-PSHP_875115452004_8X8,7"))
    )
    (comp (ref "C808")
      (value "150u")
      (footprint "eagle-import:4.2X1.9X2.8(BXCXA)")
      (libsource (lib "eagle-import") (part "WCAP-PSHP_875115452004_8X8,7"))
    )
    (comp (ref "C809")
      (value "10n")
      (footprint "eagle-import:CAPC2012X95N")
      (libsource (lib "eagle-import") (part "C-EUC0805N"))
    )
    (comp (ref "C810")
      (value "10n")
      (footprint "eagle-import:CAPC2012X95N")
      (libsource (lib "eagle-import") (part "C-EUC0805N"))
    )
    (comp (ref "C811")
      (value "100n")
      (footprint "eagle-import:CAPC2012X95N")
      (libsource (lib "eagle-import") (part "C-EUC0805N"))
    )
    (comp (ref "C812")
      (value "100n")
      (footprint "eagle-import:CAPC2012X95N")
      (libsource (lib "eagle-import") (part "C-EUC0805N"))
    )
    (comp (ref "IC801")
      (value "TI-DRV8814PW")
      (footprint "eagle-import:SOP29P65_970X640X120L60X24T500X270N")
      (libsource (lib "eagle-import") (part "TI-DRV8814PW"))
    )
    (comp (ref "IC802")
      (value "TI-DRV8814PW")
      (footprint "eagle-import:SOP29P65_970X640X120L60X24T500X270N")
      (libsource (lib "eagle-import") (part "TI-DRV8814PW"))
    )
    (comp (ref "J801")
      (value "WE-610004243021")
      (footprint "eagle-import:610X04243021")
      (libsource (lib "eagle-import") (part "610X04243021"))
    )
    (comp (ref "J802")
      (value "WE-610004243021")
      (footprint "eagle-import:610X04243021")
      (libsource (lib "eagle-import") (part "610X04243021"))
    )
    (comp (ref "R801")
      (value "1k0")
      (footprint "eagle-import:CAPCAF80P160X320X70-8L")
      (libsource (lib "eagle-import") (part "CTS-74,2C083"))
    )
    (comp (ref "R802")
      (value "1k0")
      (footprint "eagle-import:CAPCAF80P160X320X70-8L")
      (libsource (lib "eagle-import") (part "CTS-74,2C083"))
    )
    (comp (ref "R803")
      (value "330m")
      (footprint "eagle-import:RESC160X320X65L50L")
      (libsource (lib "eagle-import") (part "R-EU-R0612L"))
    )
    (comp (ref "R804")
      (value "330m")
      (footprint "eagle-import:RESC160X320X65L50L")
      (libsource (lib "eagle-import") (part "R-EU-R0612L"))
    )
    (comp (ref "R805")
      (value "330m")
      (footprint "eagle-import:RESC160X320X65L50L")
      (libsource (lib "eagle-import") (part "R-EU-R0612L"))
    )
    (comp (ref "R806")
      (value "330m")
      (footprint "eagle-import:RESC160X320X65L50L")
      (libsource (lib "eagle-import") (part "R-EU-R0612L"))
    )
    (comp (ref "R807")
      (value "1M0")
      (footprint "eagle-import:RESC2012X50N")
      (libsource (lib "eagle-import") (part "R-EU-R0805N"))
    )
    (comp (ref "R808")
      (value "1M0")
      (footprint "eagle-import:RESC2012X50N")
      (libsource (lib "eagle-import") (part "R-EU-R0805N"))
    )
    (comp (ref "J201")
      (value "WE-690367280476")
      (footprint "eagle-import:690367280476")
      (fields (field (name "MYNANE") "Sensor00"))
      (libsource (lib "eagle-import") (part "690367280476"))
    )
    (comp (ref "J202")
      (value "WE-690367280476")
      (footprint "eagle-import:690367280476")
      (fields (field (name "MYNANE") "Sensor15"))
      (libsource (lib "eagle-import") (part "690367280476"))
    )
    (comp (ref "J203")
      (value "WE-690367280476")
      (footprint "eagle-import:690367280476")
      (fields (field (name "MYNANE") "Sensor01"))
      (libsource (lib "eagle-import") (part "690367280476"))
    )
    (comp (ref "J204")
      (value "WE-690367280476")
      (footprint "eagle-import:690367280476")
      (fields (field (name "MYNANE") "Sensor14"))
      (libsource (lib "eagle-import") (part "690367280476"))
    )
    (comp (ref "J205")
      (value "WE-690367280476")
      (footprint "eagle-import:690367280476")
      (fields (field (name "MYNANE") "Sensor02"))
      (libsource (lib "eagle-import") (part "690367280476"))
    )
    (comp (ref "J206")
      (value "WE-690367280476")
      (footprint "eagle-import:690367280476")
      (fields (field (name "MYNANE") "Sensor13"))
      (libsource (lib "eagle-import") (part "690367280476"))
    )
    (comp (ref "J207")
      (value "WE-690367280476")
      (footprint "eagle-import:690367280476")
      (fields (field (name "MYNANE") "Sensor03"))
      (libsource (lib "eagle-import") (part "690367280476"))
    )
    (comp (ref "J208")
      (value "WE-690367280476")
      (footprint "eagle-import:690367280476")
      (fields (field (name "MYNANE") "Sensor12"))
      (libsource (lib "eagle-import") (part "690367280476"))
    )
    (comp (ref "J209")
      (value "WE-690367280476")
      (footprint "eagle-import:690367280476")
      (fields (field (name "MYNANE") "Sensor04"))
      (libsource (lib "eagle-import") (part "690367280476"))
    )
    (comp (ref "J210")
      (value "WE-690367280476")
      (footprint "eagle-import:690367280476")
      (fields (field (name "MYNANE") "Sensor11"))
      (libsource (lib "eagle-import") (part "690367280476"))
    )
    (comp (ref "J211")
      (value "WE-690367280476")
      (footprint "eagle-import:690367280476")
      (fields (field (name "MYNANE") "Sensor05"))
      (libsource (lib "eagle-import") (part "690367280476"))
    )
    (comp (ref "J212")
      (value "WE-690367280476")
      (footprint "eagle-import:690367280476")
      (fields (field (name "MYNANE") "Sensor10"))
      (libsource (lib "eagle-import") (part "690367280476"))
    )
    (comp (ref "J213")
      (value "WE-690367280476")
      (footprint "eagle-import:690367280476")
      (fields (field (name "MYNANE") "Sensor06"))
      (libsource (lib "eagle-import") (part "690367280476"))
    )
    (comp (ref "J214")
      (value "WE-690367280476")
      (footprint "eagle-import:690367280476")
      (fields (field (name "MYNANE") "Sensor09"))
      (libsource (lib "eagle-import") (part "690367280476"))
    )
    (comp (ref "J215")
      (value "WE-690367280476")
      (footprint "eagle-import:690367280476")
      (fields (field (name "MYNANE") "Sensor07"))
      (libsource (lib "eagle-import") (part "690367280476"))
    )
    (comp (ref "J216")
      (value "WE-690367280476")
      (footprint "eagle-import:690367280476")
      (fields (field (name "MYNANE") "Sensor08"))
      (libsource (lib "eagle-import") (part "690367280476"))
    )
    (comp (ref "C701")
      (value "1u0")
      (footprint "eagle-import:CAPC2012X95N")
      (libsource (lib "eagle-import") (part "C-EUC0805N"))
    )
    (comp (ref "C702")
      (value "1u0")
      (footprint "eagle-import:CAPC2012X95N")
      (libsource (lib "eagle-import") (part "C-EUC0805N"))
    )
    (comp (ref "IC701")
      (value "PCA9555PW")
      (footprint "eagle-import:TSSOP24")
      (libsource (lib "eagle-import") (part "PCA9555PW"))
    )
    (comp (ref "IC702")
      (value "PCA9555PW")
      (footprint "eagle-import:TSSOP24")
      (libsource (lib "eagle-import") (part "PCA9555PW"))
    )
    (comp (ref "IC703")
      (value "74LV32PW")
      (footprint "eagle-import:SOP14P65_500X640X120L62X24L")
      (libsource (lib "eagle-import") (part "7432PWLV"))
    )
    (comp (ref "IC704")
      (value "74LV32PW")
      (footprint "eagle-import:SOP14P65_500X640X120L62X24L")
      (libsource (lib "eagle-import") (part "7432PWLV"))
    )
    (comp (ref "J701")
      (value "WE-691305140008")
      (footprint "eagle-import:691305140008")
      (libsource (lib "eagle-import") (part "691305140008"))
    )
    (comp (ref "J702")
      (value "WE-691305140008")
      (footprint "eagle-import:691305140008")
      (libsource (lib "eagle-import") (part "691305140008"))
    )
    (comp (ref "LED701")
      (value "green")
      (footprint "eagle-import:LED-0603")
      (libsource (lib "eagle-import") (part "LED0603"))
    )
    (comp (ref "LED702")
      (value "green")
      (footprint "eagle-import:LED-0603")
      (libsource (lib "eagle-import") (part "LED0603"))
    )
    (comp (ref "LED703")
      (value "green")
      (footprint "eagle-import:LED-0603")
      (libsource (lib "eagle-import") (part "LED0603"))
    )
    (comp (ref "LED704")
      (value "yellow")
      (footprint "eagle-import:LED-0603")
      (libsource (lib "eagle-import") (part "LED0603"))
    )
    (comp (ref "LED705")
      (value "green")
      (footprint "eagle-import:LED-0603")
      (libsource (lib "eagle-import") (part "LED0603"))
    )
    (comp (ref "LED706")
      (value "green")
      (footprint "eagle-import:LED-0603")
      (libsource (lib "eagle-import") (part "LED0603"))
    )
    (comp (ref "LED707")
      (value "green")
      (footprint "eagle-import:LED-0603")
      (libsource (lib "eagle-import") (part "LED0603"))
    )
    (comp (ref "LED708")
      (value "yellow")
      (footprint "eagle-import:LED-0603")
      (libsource (lib "eagle-import") (part "LED0603"))
    )
    (comp (ref "R701")
      (value "1k0")
      (footprint "eagle-import:CAPCAF80P160X320X70-8L")
      (libsource (lib "eagle-import") (part "CTS-74,2C083"))
    )
    (comp (ref "R702")
      (value "1k0")
      (footprint "eagle-import:CAPCAF80P160X320X70-8L")
      (libsource (lib "eagle-import") (part "CTS-74,2C083"))
    )
    (comp (ref "R703")
      (value "1k0")
      (footprint "eagle-import:CAPCAF80P160X320X70-8L")
      (libsource (lib "eagle-import") (part "CTS-74,2C083"))
    )
    (comp (ref "R704")
      (value "1k0")
      (footprint "eagle-import:CAPCAF80P160X320X70-8L")
      (libsource (lib "eagle-import") (part "CTS-74,2C083"))
    )
  )
  (nets
    (net (code "58") (name "+3V3") (class "Default")
      (node (ref "C402") (pin "1") (pinfunction "1_1") (pintype "passive"))
      (node (ref "C701") (pin "1") (pinfunction "1_1") (pintype "passive"))
      (node (ref "C702") (pin "1") (pinfunction "1_1") (pintype "passive"))
      (node (ref "C801") (pin "2") (pinfunction "2_2") (pintype "passive"))
      (node (ref "C802") (pin "2") (pinfunction "2_2") (pintype "passive"))
      (node (ref "C901") (pin "2") (pinfunction "2_2") (pintype "passive"))
      (node (ref "IC401") (pin "13") (pinfunction "VDD_13") (pintype "bidirectional"))
      (node (ref "IC701") (pin "21") (pinfunction "A0_21") (pintype "input"))
      (node (ref "IC701") (pin "24") (pinfunction "VDD_24") (pintype "power_in"))
      (node (ref "IC702") (pin "24") (pinfunction "VDD_24") (pintype "power_in"))
      (node (ref "IC703") (pin "14") (pinfunction "VCC_14") (pintype "power_in"))
      (node (ref "IC704") (pin "14") (pinfunction "VCC_14") (pintype "power_in"))
      (node (ref "IC801") (pin "15") (pinfunction "V3.3_15") (pintype "power_in"))
      (node (ref "IC801") (pin "16") (pinfunction "~{RESET}_16") (pintype "input"))
      (node (ref "IC801") (pin "17") (pinfunction "~{SLEEP}_17") (pintype "input"))
      (node (ref "IC801") (pin "19") (pinfunction "DECAY_19") (pintype "input"))
      (node (ref "IC802") (pin "15") (pinfunction "V3.3_15") (pintype "power_in"))
      (node (ref "IC802") (pin "16") (pinfunction "~{RESET}_16") (pintype "input"))
      (node (ref "IC802") (pin "17") (pinfunction "~{SLEEP}_17") (pintype "input"))
      (node (ref "IC802") (pin "19") (pinfunction "DECAY_19") (pintype "input"))
      (node (ref "IC901") (pin "15") (pinfunction "V3.3_15") (pintype "power_in"))
      (node (ref "IC901") (pin "16") (pinfunction "~{RESET}_16") (pintype "input"))
      (node (ref "IC901") (pin "17") (pinfunction "~{SLEEP}_17") (pintype "input"))
      (node (ref "IC901") (pin "19") (pinfunction "DECAY_19") (pintype "input"))
      (node (ref "J1") (pin "1") (pinfunction "1_1") (pintype "passive"))
      (node (ref "J1") (pin "17") (pinfunction "9_17") (pintype "passive"))
      (node (ref "J501") (pin "1") (pinfunction "20_1") (pintype "passive"))
      (node (ref "J501") (pin "17") (pinfunction "12_17") (pintype "passive"))
      (node (ref "R401") (pin "2") (pinfunction "2_2") (pintype "passive"))
      (node (ref "R402") (pin "2") (pinfunction "2_2") (pintype "passive"))
      (node (ref "R8") (pin "5") (pinfunction "2_5") (pintype "passive"))
      (node (ref "R8") (pin "6") (pinfunction "2_6") (pintype "passive"))
      (node (ref "R8") (pin "7") (pinfunction "2_7") (pintype "passive"))
      (node (ref "R8") (pin "8") (pinfunction "2_8") (pintype "passive"))
      (node (ref "R801") (pin "6") (pinfunction "2_6") (pintype "passive"))
      (node (ref "R801") (pin "7") (pinfunction "2_7") (pintype "passive"))
      (node (ref "R802") (pin "6") (pinfunction "2_6") (pintype "passive"))
      (node (ref "R802") (pin "7") (pinfunction "2_7") (pintype "passive"))
      (node (ref "R901") (pin "6") (pinfunction "2_6") (pintype "passive"))
      (node (ref "R901") (pin "7") (pinfunction "2_7") (pintype "passive"))
      (node (ref "S1") (pin "C1") (pinfunction "C1_C1") (pintype "passive"))
      (node (ref "S1") (pin "C2") (pinfunction "C2_C2") (pintype "passive"))
      (node (ref "SJ403") (pin "1") (pinfunction "1_1") (pintype "passive"))
    )
    (net (code "59") (name "+5V") (class "Default")
      (node (ref "C102") (pin "1") (pinfunction "1_1") (pintype "passive"))
      (node (ref "C105") (pin "1") (pinfunction "1_1") (pintype "passive"))
      (node (ref "C106") (pin "1") (pinfunction "1_1") (pintype "passive"))
      (node (ref "IC301") (pin "16") (pinfunction "VCC_16") (pintype "power_in"))
      (node (ref "IC302") (pin "16") (pinfunction "VCC_16") (pintype "power_in"))
      (node (ref "IC303") (pin "16") (pinfunction "VCC_16") (pintype "power_in"))
      (node (ref "IC304") (pin "16") (pinfunction "VCC_16") (pintype "power_in"))
      (node (ref "J1") (pin "2") (pinfunction "20_2") (pintype "passive"))
      (node (ref "J1") (pin "4") (pinfunction "19_4") (pintype "passive"))
      (node (ref "J2") (pin "2") (pinfunction "20_2") (pintype "passive"))
      (node (ref "J2") (pin "4") (pinfunction "19_4") (pintype "passive"))
      (node (ref "J201") (pin "1") (pinfunction "4_1") (pintype "passive"))
      (node (ref "J202") (pin "1") (pinfunction "4_1") (pintype "passive"))
      (node (ref "J203") (pin "1") (pinfunction "4_1") (pintype "passive"))
      (node (ref "J204") (pin "1") (pinfunction "4_1") (pintype "passive"))
      (node (ref "J205") (pin "1") (pinfunction "4_1") (pintype "passive"))
      (node (ref "J206") (pin "1") (pinfunction "4_1") (pintype "passive"))
      (node (ref "J207") (pin "1") (pinfunction "4_1") (pintype "passive"))
      (node (ref "J208") (pin "1") (pinfunction "4_1") (pintype "passive"))
      (node (ref "J209") (pin "1") (pinfunction "4_1") (pintype "passive"))
      (node (ref "J210") (pin "1") (pinfunction "4_1") (pintype "passive"))
      (node (ref "J211") (pin "1") (pinfunction "4_1") (pintype "passive"))
      (node (ref "J212") (pin "1") (pinfunction "4_1") (pintype "passive"))
      (node (ref "J213") (pin "1") (pinfunction "4_1") (pintype "passive"))
      (node (ref "J214") (pin "1") (pinfunction "4_1") (pintype "passive"))
      (node (ref "J215") (pin "1") (pinfunction "4_1") (pintype "passive"))
      (node (ref "J216") (pin "1") (pinfunction "4_1") (pintype "passive"))
      (node (ref "J501") (pin "2") (pinfunction "1_2") (pintype "passive"))
      (node (ref "J501") (pin "4") (pinfunction "2_4") (pintype "passive"))
      (node (ref "J601") (pin "2") (pinfunction "1_2") (pintype "passive"))
      (node (ref "J601") (pin "4") (pinfunction "2_4") (pintype "passive"))
      (node (ref "R103") (pin "1") (pinfunction "1_1") (pintype "passive"))
      (node (ref "U101") (pin "7") (pinfunction "7VOUT_7") (pintype "bidirectional"))
    )
    (net (code "60") (name "+12V") (class "Default")
      (node (ref "C104") (pin "1") (pinfunction "1_1") (pintype "passive"))
      (node (ref "C803") (pin "2") (pinfunction "2_2") (pintype "passive"))
      (node (ref "C804") (pin "2") (pinfunction "2_2") (pintype "passive"))
      (node (ref "C805") (pin "2") (pinfunction "2_2") (pintype "passive"))
      (node (ref "C806") (pin "2") (pinfunction "2_2") (pintype "passive"))
      (node (ref "C807") (pin "1") (pinfunction "1_1") (pintype "passive"))
      (node (ref "C808") (pin "1") (pinfunction "1_1") (pintype "passive"))
      (node (ref "C811") (pin "1") (pinfunction "1_1") (pintype "passive"))
      (node (ref "C812") (pin "1") (pinfunction "1_1") (pintype "passive"))
      (node (ref "C902") (pin "2") (pinfunction "2_2") (pintype "passive"))
      (node (ref "C903") (pin "2") (pinfunction "2_2") (pintype "passive"))
      (node (ref "C904") (pin "1") (pinfunction "1_1") (pintype "passive"))
      (node (ref "C906") (pin "1") (pinfunction "1_1") (pintype "passive"))
      (node (ref "IC801") (pin "11") (pinfunction "VM_11") (pintype "power_in"))
      (node (ref "IC801") (pin "4") (pinfunction "VM_4") (pintype "power_in"))
      (node (ref "IC802") (pin "11") (pinfunction "VM_11") (pintype "power_in"))
      (node (ref "IC802") (pin "4") (pinfunction "VM_4") (pintype "power_in"))
      (node (ref "IC901") (pin "11") (pinfunction "VM_11") (pintype "power_in"))
      (node (ref "IC901") (pin "4") (pinfunction "VM_4") (pintype "power_in"))
      (node (ref "J101") (pin "1") (pinfunction "1_1") (pintype "passive"))
      (node (ref "R102") (pin "2") (pinfunction "2_2") (pintype "passive"))
      (node (ref "R807") (pin "2") (pinfunction "2_2") (pintype "passive"))
      (node (ref "R808") (pin "2") (pinfunction "2_2") (pintype "passive"))
      (node (ref "R904") (pin "2") (pinfunction "2_2") (pintype "passive"))
      (node (ref "U101") (pin "1") (pinfunction "1VIN_1") (pintype "bidirectional"))
    )
    (net (code "73") (name "ADO") (class "Default")
      (node (ref "IC401") (pin "9") (pinfunction "AD0_9") (pintype "bidirectional"))
      (node (ref "SJ403") (pin "2") (pinfunction "2_2") (pintype "passive"))
    )
    (net (code "74") (name "CLKIN") (class "Default")
      (node (ref "IC401") (pin "1") (pinfunction "CLKIN_1") (pintype "bidirectional"))
      (node (ref "SJ402") (pin "2") (pinfunction "2_2") (pintype "passive"))
    )
    (net (code "75") (name "FSYNC") (class "Default")
      (node (ref "IC401") (pin "11") (pinfunction "FSYNC_11") (pintype "bidirectional"))
      (node (ref "SJ401") (pin "2") (pinfunction "2_2") (pintype "passive"))
    )
    (net (code "76") (name "GND") (class "Default")
      (node (ref "C101") (pin "1") (pinfunction "1_1") (pintype "passive"))
      (node (ref "C103") (pin "2") (pinfunction "2_2") (pintype "passive"))
      (node (ref "C104") (pin "2") (pinfunction "2_2") (pintype "passive"))
      (node (ref "C105") (pin "2") (pinfunction "2_2") (pintype "passive"))
      (node (ref "C106") (pin "2") (pinfunction "2_2") (pintype "passive"))
      (node (ref "C401") (pin "2") (pinfunction "2_2") (pintype "passive"))
      (node (ref "C402") (pin "2") (pinfunction "2_2") (pintype "passive"))
      (node (ref "C403") (pin "2") (pinfunction "2_2") (pintype "passive"))
      (node (ref "C404") (pin "2") (pinfunction "2_2") (pintype "passive"))
      (node (ref "C701") (pin "2") (pinfunction "2_2") (pintype "passive"))
      (node (ref "C702") (pin "2") (pinfunction "2_2") (pintype "passive"))
      (node (ref "C801") (pin "1") (pinfunction "1_1") (pintype "passive"))
      (node (ref "C802") (pin "1") (pinfunction "1_1") (pintype "passive"))
      (node (ref "C803") (pin "1") (pinfunction "1_1") (pintype "passive"))
      (node (ref "C804") (pin "1") (pinfunction "1_1") (pintype "passive"))
      (node (ref "C805") (pin "1") (pinfunction "1_1") (pintype "passive"))
      (node (ref "C806") (pin "1") (pinfunction "1_1") (pintype "passive"))
      (node (ref "C807") (pin "2") (pinfunction "2_2") (pintype "passive"))
      (node (ref "C808") (pin "2") (pinfunction "2_2") (pintype "passive"))
      (node (ref "C901") (pin "1") (pinfunction "1_1") (pintype "passive"))
      (node (ref "C902") (pin "1") (pinfunction "1_1") (pintype "passive"))
      (node (ref "C903") (pin "1") (pinfunction "1_1") (pintype "passive"))
      (node (ref "C904") (pin "2") (pinfunction "2_2") (pintype "passive"))
      (node (ref "IC301") (pin "6") (pinfunction "~{OE}_6") (pintype "input"))
      (node (ref "IC301") (pin "7") (pinfunction "GND_7") (pintype "power_in"))
      (node (ref "IC301") (pin "8") (pinfunction "GND_8") (pintype "power_in"))
      (node (ref "IC302") (pin "6") (pinfunction "~{OE}_6") (pintype "input"))
      (node (ref "IC302") (pin "7") (pinfunction "GND_7") (pintype "power_in"))
      (node (ref "IC302") (pin "8") (pinfunction "GND_8") (pintype "power_in"))
      (node (ref "IC303") (pin "6") (pinfunction "~{OE}_6") (pintype "input"))
      (node (ref "IC303") (pin "7") (pinfunction "GND_7") (pintype "power_in"))
      (node (ref "IC303") (pin "8") (pinfunction "GND_8") (pintype "power_in"))
      (node (ref "IC304") (pin "6") (pinfunction "~{OE}_6") (pintype "input"))
      (node (ref "IC304") (pin "7") (pinfunction "GND_7") (pintype "power_in"))
      (node (ref "IC304") (pin "8") (pinfunction "GND_8") (pintype "power_in"))
      (node (ref "IC401") (pin "18") (pinfunction "GND_18") (pintype "bidirectional"))
      (node (ref "IC701") (pin "12") (pinfunction "VSS_12") (pintype "power_in"))
      (node (ref "IC701") (pin "2") (pinfunction "A1_2") (pintype "input"))
      (node (ref "IC701") (pin "3") (pinfunction "A2_3") (pintype "input"))
      (node (ref "IC702") (pin "12") (pinfunction "VSS_12") (pintype "power_in"))
      (node (ref "IC702") (pin "2") (pinfunction "A1_2") (pintype "input"))
      (node (ref "IC702") (pin "21") (pinfunction "A0_21") (pintype "input"))
      (node (ref "IC702") (pin "3") (pinfunction "A2_3") (pintype "input"))
      (node (ref "IC703") (pin "7") (pinfunction "GND_7") (pintype "power_in"))
      (node (ref "IC704") (pin "10") (pinfunction "I1_10") (pintype "input"))
      (node (ref "IC704") (pin "12") (pinfunction "I0_12") (pintype "input"))
      (node (ref "IC704") (pin "13") (pinfunction "I1_13") (pintype "input"))
      (node (ref "IC704") (pin "7") (pinfunction "GND_7") (pintype "power_in"))
      (node (ref "IC704") (pin "9") (pinfunction "I0_9") (pintype "input"))
      (node (ref "IC801") (pin "14") (pinfunction "GND_14") (pintype "power_in"))
      (node (ref "IC801") (pin "28") (pinfunction "GND_28") (pintype "power_in"))
      (node (ref "IC801") (pin "29") (pinfunction "GND_29") (pintype "power_in"))
      (node (ref "IC802") (pin "14") (pinfunction "GND_14") (pintype "power_in"))
      (node (ref "IC802") (pin "28") (pinfunction "GND_28") (pintype "power_in"))
      (node (ref "IC802") (pin "29") (pinfunction "GND_29") (pintype "power_in"))
      (node (ref "IC901") (pin "14") (pinfunction "GND_14") (pintype "power_in"))
      (node (ref "IC901") (pin "28") (pinfunction "GND_28") (pintype "power_in"))
      (node (ref "IC901") (pin "29") (pinfunction "GND_29") (pintype "power_in"))
      (node (ref "J1") (pin "14") (pinfunction "14_14") (pintype "passive"))
      (node (ref "J1") (pin "20") (pinfunction "11_20") (pintype "passive"))
      (node (ref "J1") (pin "6") (pinfunction "18_6") (pintype "passive"))
      (node (ref "J1") (pin "9") (pinfunction "5_9") (pintype "passive"))
      (node (ref "J101") (pin "2") (pinfunction "2_2") (pintype "passive"))
      (node (ref "J101") (pin "3") (pinfunction "3_3") (pintype "passive"))
      (node (ref "J2") (pin "14") (pinfunction "14_14") (pintype "passive"))
      (node (ref "J2") (pin "20") (pinfunction "11_20") (pintype "passive"))
      (node (ref "J2") (pin "6") (pinfunction "18_6") (pintype "passive"))
      (node (ref "J2") (pin "9") (pinfunction "5_9") (pintype "passive"))
      (node (ref "J201") (pin "4") (pinfunction "1_4") (pintype "passive"))
      (node (ref "J202") (pin "4") (pinfunction "1_4") (pintype "passive"))
      (node (ref "J203") (pin "4") (pinfunction "1_4") (pintype "passive"))
      (node (ref "J204") (pin "4") (pinfunction "1_4") (pintype "passive"))
      (node (ref "J205") (pin "4") (pinfunction "1_4") (pintype "passive"))
      (node (ref "J206") (pin "4") (pinfunction "1_4") (pintype "passive"))
      (node (ref "J207") (pin "4") (pinfunction "1_4") (pintype "passive"))
      (node (ref "J208") (pin "4") (pinfunction "1_4") (pintype "passive"))
      (node (ref "J209") (pin "4") (pinfunction "1_4") (pintype "passive"))
      (node (ref "J210") (pin "4") (pinfunction "1_4") (pintype "passive"))
      (node (ref "J211") (pin "4") (pinfunction "1_4") (pintype "passive"))
      (node (ref "J212") (pin "4") (pinfunction "1_4") (pintype "passive"))
      (node (ref "J213") (pin "4") (pinfunction "1_4") (pintype "passive"))
      (node (ref "J214") (pin "4") (pinfunction "1_4") (pintype "passive"))
      (node (ref "J215") (pin "4") (pinfunction "1_4") (pintype "passive"))
      (node (ref "J216") (pin "4") (pinfunction "1_4") (pintype "passive"))
      (node (ref "J3") (pin "10") (pinfunction "16_10") (pintype "passive"))
      (node (ref "J3") (pin "14") (pinfunction "14_14") (pintype "passive"))
      (node (ref "J3") (pin "19") (pinfunction "10_19") (pintype "passive"))
      (node (ref "J3") (pin "5") (pinfunction "3_5") (pintype "passive"))
      (node (ref "J4") (pin "10") (pinfunction "16_10") (pintype "passive"))
      (node (ref "J4") (pin "14") (pinfunction "14_14") (pintype "passive"))
      (node (ref "J4") (pin "19") (pinfunction "10_19") (pintype "passive"))
      (node (ref "J4") (pin "5") (pinfunction "3_5") (pintype "passive"))
      (node (ref "J501") (pin "14") (pinfunction "7_14") (pintype "passive"))
      (node (ref "J501") (pin "20") (pinfunction "10_20") (pintype "passive"))
      (node (ref "J501") (pin "6") (pinfunction "3_6") (pintype "passive"))
      (node (ref "J501") (pin "9") (pinfunction "16_9") (pintype "passive"))
      (node (ref "J502") (pin "10") (pinfunction "5_10") (pintype "passive"))
      (node (ref "J502") (pin "14") (pinfunction "7_14") (pintype "passive"))
      (node (ref "J502") (pin "19") (pinfunction "11_19") (pintype "passive"))
      (node (ref "J502") (pin "5") (pinfunction "18_5") (pintype "passive"))
      (node (ref "J601") (pin "14") (pinfunction "7_14") (pintype "passive"))
      (node (ref "J601") (pin "20") (pinfunction "10_20") (pintype "passive"))
      (node (ref "J601") (pin "6") (pinfunction "3_6") (pintype "passive"))
      (node (ref "J601") (pin "9") (pinfunction "16_9") (pintype "passive"))
      (node (ref "J602") (pin "10") (pinfunction "5_10") (pintype "passive"))
      (node (ref "J602") (pin "14") (pinfunction "7_14") (pintype "passive"))
      (node (ref "J602") (pin "19") (pinfunction "11_19") (pintype "passive"))
      (node (ref "J602") (pin "5") (pinfunction "18_5") (pintype "passive"))
      (node (ref "J801") (pin "1") (pinfunction "1_1") (pintype "passive"))
      (node (ref "J801") (pin "3") (pinfunction "2_3") (pintype "passive"))
      (node (ref "J802") (pin "1") (pinfunction "1_1") (pintype "passive"))
      (node (ref "J802") (pin "3") (pinfunction "2_3") (pintype "passive"))
      (node (ref "J901") (pin "1") (pinfunction "1_1") (pintype "passive"))
      (node (ref "J901") (pin "3") (pinfunction "2_3") (pintype "passive"))
      (node (ref "R1") (pin "3") (pinfunction "1_3") (pintype "passive"))
      (node (ref "R101") (pin "1") (pinfunction "1_1") (pintype "passive"))
      (node (ref "R2") (pin "6") (pinfunction "2_6") (pintype "passive"))
      (node (ref "R7") (pin "1") (pinfunction "1_1") (pintype "passive"))
      (node (ref "R7") (pin "2") (pinfunction "1_2") (pintype "passive"))
      (node (ref "R7") (pin "3") (pinfunction "1_3") (pintype "passive"))
      (node (ref "R7") (pin "4") (pinfunction "1_4") (pintype "passive"))
      (node (ref "R701") (pin "1") (pinfunction "1_1") (pintype "passive"))
      (node (ref "R701") (pin "2") (pinfunction "1_2") (pintype "passive"))
      (node (ref "R701") (pin "3") (pinfunction "1_3") (pintype "passive"))
      (node (ref "R701") (pin "4") (pinfunction "1_4") (pintype "passive"))
      (node (ref "R702") (pin "1") (pinfunction "1_1") (pintype "passive"))
      (node (ref "R702") (pin "2") (pinfunction "1_2") (pintype "passive"))
      (node (ref "R702") (pin "3") (pinfunction "1_3") (pintype "passive"))
      (node (ref "R702") (pin "4") (pinfunction "1_4") (pintype "passive"))
      (node (ref "R703") (pin "1") (pinfunction "1_1") (pintype "passive"))
      (node (ref "R703") (pin "2") (pinfunction "1_2") (pintype "passive"))
      (node (ref "R703") (pin "3") (pinfunction "1_3") (pintype "passive"))
      (node (ref "R703") (pin "4") (pinfunction "1_4") (pintype "passive"))
      (node (ref "R704") (pin "1") (pinfunction "1_1") (pintype "passive"))
      (node (ref "R704") (pin "2") (pinfunction "1_2") (pintype "passive"))
      (node (ref "R704") (pin "3") (pinfunction "1_3") (pintype "passive"))
      (node (ref "R704") (pin "4") (pinfunction "1_4") (pintype "passive"))
      (node (ref "R801") (pin "5") (pinfunction "2_5") (pintype "passive"))
      (node (ref "R801") (pin "8") (pinfunction "2_8") (pintype "passive"))
      (node (ref "R802") (pin "5") (pinfunction "2_5") (pintype "passive"))
      (node (ref "R802") (pin "8") (pinfunction "2_8") (pintype "passive"))
      (node (ref "R803") (pin "2") (pinfunction "2_2") (pintype "passive"))
      (node (ref "R804") (pin "2") (pinfunction "2_2") (pintype "passive"))
      (node (ref "R805") (pin "2") (pinfunction "2_2") (pintype "passive"))
      (node (ref "R806") (pin "2") (pinfunction "2_2") (pintype "passive"))
      (node (ref "R901") (pin "5") (pinfunction "2_5") (pintype "passive"))
      (node (ref "R901") (pin "8") (pinfunction "2_8") (pintype "passive"))
      (node (ref "R902") (pin "2") (pinfunction "2_2") (pintype "passive"))
      (node (ref "R903") (pin "2") (pinfunction "2_2") (pintype "passive"))
      (node (ref "S2") (pin "3") (pinfunction "2_3") (pintype "passive"))
      (node (ref "S2") (pin "4") (pinfunction "4_4") (pintype "passive"))
      (node (ref "S3") (pin "3") (pinfunction "2_3") (pintype "passive"))
      (node (ref "S3") (pin "4") (pinfunction "4_4") (pintype "passive"))
      (node (ref "SJ401") (pin "1") (pinfunction "1_1") (pintype "passive"))
      (node (ref "SJ402") (pin "1") (pinfunction "1_1") (pintype "passive"))
      (node (ref "SJ403") (pin "3") (pinfunction "3_3") (pintype "passive"))
      (node (ref "U101") (pin "4") (pinfunction "4AGND_4") (pintype "bidirectional"))
      (node (ref "U101") (pin "EP") (pinfunction "PGND_EP") (pintype "bidirectional"))
    )
    (net (code "77") (name "GPIO0") (class "Default")
      (node (ref "J1") (pin "11") (pinfunction "6_11") (pintype "passive"))
      (node (ref "J501") (pin "11") (pinfunction "15_11") (pintype "passive"))
      (node (ref "R2") (pin "2") (pinfunction "1_2") (pintype "passive"))
      (node (ref "R2") (pin "8") (pinfunction "2_8") (pintype "passive"))
    )
    (net (code "78") (name "GPIO1") (class "Default")
      (node (ref "J1") (pin "12") (pinfunction "15_12") (pintype "passive"))
      (node (ref "J501") (pin "12") (pinfunction "6_12") (pintype "passive"))
      (node (ref "R2") (pin "4") (pinfunction "1_4") (pintype "passive"))
      (node (ref "R3") (pin "1") (pinfunction "1_1") (pintype "passive"))
    )
    (net (code "79") (name "GPIO2") (class "Default")
      (node (ref "IC301") (pin "11") (pinfunction "S0_11") (pintype "input"))
      (node (ref "IC302") (pin "11") (pinfunction "S0_11") (pintype "input"))
      (node (ref "J1") (pin "13") (pinfunction "7_13") (pintype "passive"))
      (node (ref "J501") (pin "13") (pinfunction "14_13") (pintype "passive"))
    )
    (net (code "80") (name "GPIO3") (class "Default")
      (node (ref "IC301") (pin "10") (pinfunction "S1_10") (pintype "input"))
      (node (ref "IC302") (pin "10") (pinfunction "S1_10") (pintype "input"))
      (node (ref "J1") (pin "15") (pinfunction "8_15") (pintype "passive"))
      (node (ref "J501") (pin "15") (pinfunction "13_15") (pintype "passive"))
    )
    (net (code "81") (name "GPIO4") (class "Default")
      (node (ref "IC301") (pin "9") (pinfunction "S2_9") (pintype "input"))
      (node (ref "IC302") (pin "9") (pinfunction "S2_9") (pintype "input"))
      (node (ref "J1") (pin "16") (pinfunction "13_16") (pintype "passive"))
      (node (ref "J501") (pin "16") (pinfunction "8_16") (pintype "passive"))
    )
    (net (code "82") (name "GPIO5") (class "Default")
      (node (ref "J1") (pin "18") (pinfunction "12_18") (pintype "passive"))
      (node (ref "J501") (pin "18") (pinfunction "9_18") (pintype "passive"))
    )
    (net (code "83") (name "GPIO6") (class "Default")
      (node (ref "J4") (pin "2") (pinfunction "20_2") (pintype "passive"))
      (node (ref "J502") (pin "2") (pinfunction "1_2") (pintype "passive"))
    )
    (net (code "84") (name "GPIO7") (class "Default")
      (node (ref "J1") (pin "7") (pinfunction "4_7") (pintype "passive"))
      (node (ref "J501") (pin "7") (pinfunction "17_7") (pintype "passive"))
    )
    (net (code "85") (name "GPIO10") (class "Default")
      (node (ref "J4") (pin "4") (pinfunction "19_4") (pintype "passive"))
      (node (ref "J502") (pin "4") (pinfunction "2_4") (pintype "passive"))
      (node (ref "R1") (pin "7") (pinfunction "2_7") (pintype "passive"))
      (node (ref "R1") (pin "8") (pinfunction "2_8") (pintype "passive"))
    )
    (net (code "86") (name "GPIO11") (class "Default")
      (node (ref "J4") (pin "6") (pinfunction "18_6") (pintype "passive"))
      (node (ref "J502") (pin "6") (pinfunction "3_6") (pintype "passive"))
      (node (ref "R1") (pin "4") (pinfunction "1_4") (pintype "passive"))
      (node (ref "R5") (pin "2") (pinfunction "2_2") (pintype "passive"))
    )
    (net (code "87") (name "GPIO12") (class "Default")
      (node (ref "IC303") (pin "11") (pinfunction "S0_11") (pintype "input"))
      (node (ref "IC304") (pin "11") (pinfunction "S0_11") (pintype "input"))
      (node (ref "J1") (pin "19") (pinfunction "10_19") (pintype "passive"))
      (node (ref "J501") (pin "19") (pinfunction "11_19") (pintype "passive"))
    )
    (net (code "88") (name "GPIO13") (class "Default")
      (node (ref "IC303") (pin "10") (pinfunction "S1_10") (pintype "input"))
      (node (ref "IC304") (pin "10") (pinfunction "S1_10") (pintype "input"))
      (node (ref "J4") (pin "1") (pinfunction "1_1") (pintype "passive"))
      (node (ref "J502") (pin "1") (pinfunction "20_1") (pintype "passive"))
    )
    (net (code "89") (name "GPIO14") (class "Default")
      (node (ref "IC303") (pin "9") (pinfunction "S2_9") (pintype "input"))
      (node (ref "IC304") (pin "9") (pinfunction "S2_9") (pintype "input"))
      (node (ref "J4") (pin "3") (pinfunction "2_3") (pintype "passive"))
      (node (ref "J502") (pin "3") (pinfunction "19_3") (pintype "passive"))
    )
    (net (code "90") (name "GPIO21") (class "Default")
      (node (ref "J4") (pin "9") (pinfunction "5_9") (pintype "passive"))
      (node (ref "J502") (pin "9") (pinfunction "16_9") (pintype "passive"))
      (node (ref "R8") (pin "3") (pinfunction "1_3") (pintype "passive"))
      (node (ref "S2") (pin "1") (pinfunction "1_1") (pintype "passive"))
    )
    (net (code "91") (name "GPIO22") (class "Default")
      (node (ref "J4") (pin "11") (pinfunction "6_11") (pintype "passive"))
      (node (ref "J502") (pin "11") (pinfunction "15_11") (pintype "passive"))
      (node (ref "R8") (pin "4") (pinfunction "1_4") (pintype "passive"))
      (node (ref "S3") (pin "1") (pinfunction "1_1") (pintype "passive"))
    )
    (net (code "92") (name "GPIO23(PWM1)") (class "Default")
      (node (ref "IC703") (pin "12") (pinfunction "I0_12") (pintype "input"))
      (node (ref "IC704") (pin "1") (pinfunction "I0_1") (pintype "input"))
      (node (ref "IC704") (pin "4") (pinfunction "I0_4") (pintype "input"))
      (node (ref "J4") (pin "13") (pinfunction "7_13") (pintype "passive"))
      (node (ref "J502") (pin "13") (pinfunction "14_13") (pintype "passive"))
      (node (ref "R704") (pin "6") (pinfunction "2_6") (pintype "passive"))
    )
    (net (code "93") (name "GPIO24") (class "Default")
      (node (ref "J4") (pin "15") (pinfunction "8_15") (pintype "passive"))
      (node (ref "J502") (pin "15") (pinfunction "13_15") (pintype "passive"))
    )
    (net (code "94") (name "GPIO25") (class "Default")
      (node (ref "J4") (pin "17") (pinfunction "9_17") (pintype "passive"))
      (node (ref "J502") (pin "17") (pinfunction "12_17") (pintype "passive"))
      (node (ref "R7") (pin "7") (pinfunction "2_7") (pintype "passive"))
      (node (ref "S1") (pin "8") (pinfunction "8_8") (pintype "passive"))
    )
    (net (code "95") (name "GPIO26(PWM0)") (class "Default")
      (node (ref "IC703") (pin "1") (pinfunction "I0_1") (pintype "input"))
      (node (ref "IC703") (pin "4") (pinfunction "I0_4") (pintype "input"))
      (node (ref "IC703") (pin "9") (pinfunction "I0_9") (pintype "input"))
      (node (ref "J4") (pin "12") (pinfunction "15_12") (pintype "passive"))
      (node (ref "J502") (pin "12") (pinfunction "6_12") (pintype "passive"))
      (node (ref "R704") (pin "5") (pinfunction "2_5") (pintype "passive"))
    )
    (net (code "96") (name "GPIO27") (class "Default")
      (node (ref "J4") (pin "16") (pinfunction "13_16") (pintype "passive"))
      (node (ref "J502") (pin "16") (pinfunction "8_16") (pintype "passive"))
      (node (ref "R7") (pin "8") (pinfunction "2_8") (pintype "passive"))
      (node (ref "S1") (pin "1") (pinfunction "1_1") (pintype "passive"))
    )
    (net (code "97") (name "GPIO28") (class "Default")
      (node (ref "J4") (pin "18") (pinfunction "12_18") (pintype "passive"))
      (node (ref "J502") (pin "18") (pinfunction "9_18") (pintype "passive"))
      (node (ref "R7") (pin "6") (pinfunction "2_6") (pintype "passive"))
      (node (ref "S1") (pin "2") (pinfunction "2_2") (pintype "passive"))
    )
    (net (code "98") (name "GPIO29") (class "Default")
      (node (ref "J4") (pin "20") (pinfunction "11_20") (pintype "passive"))
      (node (ref "J502") (pin "20") (pinfunction "10_20") (pintype "passive"))
      (node (ref "R7") (pin "5") (pinfunction "2_5") (pintype "passive"))
      (node (ref "S1") (pin "4") (pinfunction "4_4") (pintype "passive"))
    )
    (net (code "99") (name "MC_DIRECTION0") (class "Default")
      (node (ref "IC702") (pin "13") (pinfunction "I/O1.0_13") (pintype "bidirectional"))
      (node (ref "IC801") (pin "20") (pinfunction "A_PHASE_20") (pintype "input"))
    )
    (net (code "100") (name "MC_DIRECTION1") (class "Default")
      (node (ref "IC702") (pin "14") (pinfunction "I/O1.1_14") (pintype "bidirectional"))
      (node (ref "IC801") (pin "23") (pinfunction "B_PHASE_23") (pintype "input"))
    )
    (net (code "101") (name "MC_DIRECTION2") (class "Default")
      (node (ref "IC702") (pin "15") (pinfunction "I/O1.2_15") (pintype "bidirectional"))
      (node (ref "IC802") (pin "20") (pinfunction "A_PHASE_20") (pintype "input"))
    )
    (net (code "102") (name "MC_DIRECTION3") (class "Default")
      (node (ref "IC702") (pin "16") (pinfunction "I/O1.3_16") (pintype "bidirectional"))
      (node (ref "IC802") (pin "23") (pinfunction "B_PHASE_23") (pintype "input"))
    )
    (net (code "103") (name "MC_DIRECTION4") (class "Default")
      (node (ref "IC702") (pin "17") (pinfunction "I/O1.4_17") (pintype "bidirectional"))
      (node (ref "IC901") (pin "20") (pinfunction "A_PHASE_20") (pintype "input"))
    )
    (net (code "104") (name "MC_DIRECTION5") (class "Default")
      (node (ref "IC702") (pin "18") (pinfunction "I/O1.5_18") (pintype "bidirectional"))
      (node (ref "IC901") (pin "23") (pinfunction "B_PHASE_23") (pintype "input"))
    )
    (net (code "105") (name "MC_I0_0") (class "Default")
      (node (ref "IC702") (pin "10") (pinfunction "I/O0.6_10") (pintype "bidirectional"))
      (node (ref "IC801") (pin "24") (pinfunction "A_I0_24") (pintype "input"))
    )
    (net (code "106") (name "MC_I0_1") (class "Default")
      (node (ref "IC702") (pin "19") (pinfunction "I/O1.6_19") (pintype "bidirectional"))
      (node (ref "IC801") (pin "26") (pinfunction "B_I0_26") (pintype "input"))
    )
    (net (code "107") (name "MC_I0_2") (class "Default")
      (node (ref "IC701") (pin "4") (pinfunction "I/O0.0_4") (pintype "bidirectional"))
      (node (ref "IC802") (pin "24") (pinfunction "A_I0_24") (pintype "input"))
    )
    (net (code "108") (name "MC_I0_3") (class "Default")
      (node (ref "IC701") (pin "6") (pinfunction "I/O0.2_6") (pintype "bidirectional"))
      (node (ref "IC802") (pin "26") (pinfunction "B_I0_26") (pintype "input"))
    )
    (net (code "109") (name "MC_I0_4") (class "Default")
      (node (ref "IC701") (pin "8") (pinfunction "I/O0.4_8") (pintype "bidirectional"))
      (node (ref "IC901") (pin "24") (pinfunction "A_I0_24") (pintype "input"))
    )
    (net (code "110") (name "MC_I0_5") (class "Default")
      (node (ref "IC701") (pin "10") (pinfunction "I/O0.6_10") (pintype "bidirectional"))
      (node (ref "IC901") (pin "26") (pinfunction "B_I0_26") (pintype "input"))
    )
    (net (code "111") (name "MC_I1_0") (class "Default")
      (node (ref "IC702") (pin "11") (pinfunction "I/O0.7_11") (pintype "bidirectional"))
      (node (ref "IC801") (pin "25") (pinfunction "A_I1_25") (pintype "input"))
    )
    (net (code "112") (name "MC_I1_1") (class "Default")
      (node (ref "IC702") (pin "20") (pinfunction "I/O1.7_20") (pintype "bidirectional"))
      (node (ref "IC801") (pin "27") (pinfunction "B_I1_27") (pintype "input"))
    )
    (net (code "113") (name "MC_I1_2") (class "Default")
      (node (ref "IC701") (pin "5") (pinfunction "I/O0.1_5") (pintype "bidirectional"))
      (node (ref "IC802") (pin "25") (pinfunction "A_I1_25") (pintype "input"))
    )
    (net (code "114") (name "MC_I1_3") (class "Default")
      (node (ref "IC701") (pin "7") (pinfunction "I/O0.3_7") (pintype "bidirectional"))
      (node (ref "IC802") (pin "27") (pinfunction "B_I1_27") (pintype "input"))
    )
    (net (code "115") (name "MC_I1_4") (class "Default")
      (node (ref "IC701") (pin "9") (pinfunction "I/O0.5_9") (pintype "bidirectional"))
      (node (ref "IC901") (pin "25") (pinfunction "A_I1_25") (pintype "input"))
    )
    (net (code "116") (name "MC_I1_5") (class "Default")
      (node (ref "IC701") (pin "11") (pinfunction "I/O0.7_11") (pintype "bidirectional"))
      (node (ref "IC901") (pin "27") (pinfunction "B_I1_27") (pintype "input"))
    )
    (net (code "117") (name "MC_ON0") (class "Default")
      (node (ref "IC703") (pin "3") (pinfunction "O_3") (pintype "output"))
      (node (ref "IC801") (pin "21") (pinfunction "A_ENABLE_21") (pintype "input"))
    )
    (net (code "118") (name "MC_ON1") (class "Default")
      (node (ref "IC703") (pin "6") (pinfunction "O_6") (pintype "output"))
      (node (ref "IC801") (pin "22") (pinfunction "B_ENABLE_22") (pintype "input"))
    )
    (net (code "119") (name "MC_ON2") (class "Default")
      (node (ref "IC703") (pin "8") (pinfunction "O_8") (pintype "output"))
      (node (ref "IC802") (pin "21") (pinfunction "A_ENABLE_21") (pintype "input"))
    )
    (net (code "120") (name "MC_ON3") (class "Default")
      (node (ref "IC703") (pin "11") (pinfunction "O_11") (pintype "output"))
      (node (ref "IC802") (pin "22") (pinfunction "B_ENABLE_22") (pintype "input"))
    )
    (net (code "121") (name "MC_ON4") (class "Default")
      (node (ref "IC704") (pin "3") (pinfunction "O_3") (pintype "output"))
      (node (ref "IC901") (pin "21") (pinfunction "A_ENABLE_21") (pintype "input"))
    )
    (net (code "122") (name "MC_ON5") (class "Default")
      (node (ref "IC704") (pin "6") (pinfunction "O_6") (pintype "output"))
      (node (ref "IC901") (pin "22") (pinfunction "B_ENABLE_22") (pintype "input"))
    )
    (net (code "123") (name "MC_ON{slash}OFF0") (class "Default")
      (node (ref "IC702") (pin "4") (pinfunction "I/O0.0_4") (pintype "bidirectional"))
      (node (ref "IC703") (pin "2") (pinfunction "I1_2") (pintype "input"))
      (node (ref "R704") (pin "7") (pinfunction "2_7") (pintype "passive"))
    )
    (net (code "124") (name "MC_ON{slash}OFF1") (class "Default")
      (node (ref "IC702") (pin "5") (pinfunction "I/O0.1_5") (pintype "bidirectional"))
      (node (ref "IC703") (pin "5") (pinfunction "I1_5") (pintype "input"))
      (node (ref "R704") (pin "8") (pinfunction "2_8") (pintype "passive"))
    )
    (net (code "125") (name "MC_ON{slash}OFF2") (class "Default")
      (node (ref "IC702") (pin "6") (pinfunction "I/O0.2_6") (pintype "bidirectional"))
      (node (ref "IC703") (pin "10") (pinfunction "I1_10") (pintype "input"))
      (node (ref "R703") (pin "5") (pinfunction "2_5") (pintype "passive"))
    )
    (net (code "126") (name "MC_ON{slash}OFF3") (class "Default")
      (node (ref "IC702") (pin "7") (pinfunction "I/O0.3_7") (pintype "bidirectional"))
      (node (ref "IC703") (pin "13") (pinfunction "I1_13") (pintype "input"))
      (node (ref "R703") (pin "6") (pinfunction "2_6") (pintype "passive"))
    )
    (net (code "127") (name "MC_ON{slash}OFF4") (class "Default")
      (node (ref "IC702") (pin "8") (pinfunction "I/O0.4_8") (pintype "bidirectional"))
      (node (ref "IC704") (pin "2") (pinfunction "I1_2") (pintype "input"))
      (node (ref "R703") (pin "7") (pinfunction "2_7") (pintype "passive"))
    )
    (net (code "128") (name "MC_ON{slash}OFF5") (class "Default")
      (node (ref "IC702") (pin "9") (pinfunction "I/O0.5_9") (pintype "bidirectional"))
      (node (ref "IC704") (pin "5") (pinfunction "I1_5") (pintype "input"))
      (node (ref "R703") (pin "8") (pinfunction "2_8") (pintype "passive"))
    )
    (net (code "129") (name "MOTOR+0") (class "Default")
      (node (ref "IC801") (pin "5") (pinfunction "AOUT1_5") (pintype "output"))
      (node (ref "J701") (pin "1") (pinfunction "8_1") (pintype "passive"))
    )
    (net (code "130") (name "MOTOR+1") (class "Default")
      (node (ref "IC801") (pin "10") (pinfunction "BOUT1_10") (pintype "output"))
      (node (ref "J701") (pin "4") (pinfunction "5_4") (pintype "passive"))
    )
    (net (code "131") (name "MOTOR+2") (class "Default")
      (node (ref "IC802") (pin "5") (pinfunction "AOUT1_5") (pintype "output"))
      (node (ref "J701") (pin "7") (pinfunction "2_7") (pintype "passive"))
    )
    (net (code "132") (name "MOTOR+3") (class "Default")
      (node (ref "IC802") (pin "10") (pinfunction "BOUT1_10") (pintype "output"))
      (node (ref "J702") (pin "1") (pinfunction "8_1") (pintype "passive"))
    )
    (net (code "133") (name "MOTOR+4") (class "Default")
      (node (ref "IC901") (pin "5") (pinfunction "AOUT1_5") (pintype "output"))
      (node (ref "J702") (pin "4") (pinfunction "5_4") (pintype "passive"))
    )
    (net (code "134") (name "MOTOR+5") (class "Default")
      (node (ref "IC901") (pin "10") (pinfunction "BOUT1_10") (pintype "output"))
      (node (ref "J702") (pin "7") (pinfunction "2_7") (pintype "passive"))
    )
    (net (code "135") (name "MOTOR-0") (class "Default")
      (node (ref "IC801") (pin "7") (pinfunction "AOUT2_7") (pintype "output"))
      (node (ref "J701") (pin "2") (pinfunction "7_2") (pintype "passive"))
    )
    (net (code "136") (name "MOTOR-1") (class "Default")
      (node (ref "IC801") (pin "8") (pinfunction "BOUT2_8") (pintype "output"))
      (node (ref "J701") (pin "5") (pinfunction "4_5") (pintype "passive"))
    )
    (net (code "137") (name "MOTOR-2") (class "Default")
      (node (ref "IC802") (pin "7") (pinfunction "AOUT2_7") (pintype "output"))
      (node (ref "J701") (pin "8") (pinfunction "1_8") (pintype "passive"))
    )
    (net (code "138") (name "MOTOR-3") (class "Default")
      (node (ref "IC802") (pin "8") (pinfunction "BOUT2_8") (pintype "output"))
      (node (ref "J702") (pin "2") (pinfunction "7_2") (pintype "passive"))
    )
    (net (code "139") (name "MOTOR-4") (class "Default")
      (node (ref "IC901") (pin "7") (pinfunction "AOUT2_7") (pintype "output"))
      (node (ref "J702") (pin "5") (pinfunction "4_5") (pintype "passive"))
    )
    (net (code "140") (name "MOTOR-5") (class "Default")
      (node (ref "IC901") (pin "8") (pinfunction "BOUT2_8") (pintype "output"))
      (node (ref "J702") (pin "8") (pinfunction "1_8") (pintype "passive"))
    )
    (net (code "141") (name "Net-(IC301-A)") (class "Default")
      (node (ref "IC301") (pin "3") (pinfunction "A_3") (pintype "output"))
      (node (ref "R2") (pin "1") (pinfunction "1_1") (pintype "passive"))
    )
    (net (code "142") (name "Net-(IC302-A)") (class "Default")
      (node (ref "IC302") (pin "3") (pinfunction "A_3") (pintype "output"))
      (node (ref "R2") (pin "5") (pinfunction "2_5") (pintype "passive"))
      (node (ref "R3") (pin "2") (pinfunction "2_2") (pintype "passive"))
    )
    (net (code "143") (name "Net-(IC303-A)") (class "Default")
      (node (ref "IC303") (pin "3") (pinfunction "A_3") (pintype "output"))
      (node (ref "R1") (pin "1") (pinfunction "1_1") (pintype "passive"))
    )
    (net (code "144") (name "Net-(IC304-A)") (class "Default")
      (node (ref "IC304") (pin "3") (pinfunction "A_3") (pintype "output"))
      (node (ref "R1") (pin "5") (pinfunction "2_5") (pintype "passive"))
      (node (ref "R5") (pin "1") (pinfunction "1_1") (pintype "passive"))
    )
    (net (code "145") (name "Net-(IC401-AUX_CL)") (class "Default")
      (node (ref "IC401") (pin "7") (pinfunction "AUX_CL_7") (pintype "bidirectional"))
      (node (ref "PIN403") (pin "_") (pinfunction "PIN__") (pintype "passive"))
    )
    (net (code "146") (name "Net-(IC401-AUX_DA)") (class "Default")
      (node (ref "IC401") (pin "6") (pinfunction "AUX_DA_6") (pintype "bidirectional"))
      (node (ref "PIN402") (pin "_") (pinfunction "PIN__") (pintype "passive"))
    )
    (net (code "147") (name "Net-(IC401-CPOUT)") (class "Default")
      (node (ref "C403") (pin "1") (pinfunction "1_1") (pintype "passive"))
      (node (ref "IC401") (pin "20") (pinfunction "CPOUT_20") (pintype "bidirectional"))
    )
    (net (code "148") (name "Net-(IC401-INT)") (class "Default")
      (node (ref "IC401") (pin "12") (pinfunction "INT_12") (pintype "bidirectional"))
      (node (ref "PIN401") (pin "_") (pinfunction "PIN__") (pintype "passive"))
    )
    (net (code "149") (name "Net-(IC401-REGOUT)") (class "Default")
      (node (ref "C401") (pin "1") (pinfunction "1_1") (pintype "passive"))
      (node (ref "IC401") (pin "10") (pinfunction "REGOUT_10") (pintype "bidirectional"))
    )
    (net (code "150") (name "Net-(IC701-I{slash}O1.0)") (class "Default")
      (node (ref "IC701") (pin "13") (pinfunction "I/O1.0_13") (pintype "bidirectional"))
      (node (ref "LED708") (pin "A") (pinfunction "A_A") (pintype "passive"))
    )
    (net (code "151") (name "Net-(IC701-I{slash}O1.1)") (class "Default")
      (node (ref "IC701") (pin "14") (pinfunction "I/O1.1_14") (pintype "bidirectional"))
      (node (ref "LED707") (pin "A") (pinfunction "A_A") (pintype "passive"))
    )
    (net (code "152") (name "Net-(IC701-I{slash}O1.2)") (class "Default")
      (node (ref "IC701") (pin "15") (pinfunction "I/O1.2_15") (pintype "bidirectional"))
      (node (ref "LED706") (pin "A") (pinfunction "A_A") (pintype "passive"))
    )
    (net (code "153") (name "Net-(IC701-I{slash}O1.3)") (class "Default")
      (node (ref "IC701") (pin "16") (pinfunction "I/O1.3_16") (pintype "bidirectional"))
      (node (ref "LED705") (pin "A") (pinfunction "A_A") (pintype "passive"))
    )
    (net (code "154") (name "Net-(IC701-I{slash}O1.4)") (class "Default")
      (node (ref "IC701") (pin "17") (pinfunction "I/O1.4_17") (pintype "bidirectional"))
      (node (ref "LED704") (pin "A") (pinfunction "A_A") (pintype "passive"))
    )
    (net (code "155") (name "Net-(IC701-I{slash}O1.5)") (class "Default")
      (node (ref "IC701") (pin "18") (pinfunction "I/O1.5_18") (pintype "bidirectional"))
      (node (ref "LED703") (pin "A") (pinfunction "A_A") (pintype "passive"))
    )
    (net (code "156") (name "Net-(IC701-I{slash}O1.6)") (class "Default")
      (node (ref "IC701") (pin "19") (pinfunction "I/O1.6_19") (pintype "bidirectional"))
      (node (ref "LED702") (pin "A") (pinfunction "A_A") (pintype "passive"))
    )
    (net (code "157") (name "Net-(IC701-I{slash}O1.7)") (class "Default")
      (node (ref "IC701") (pin "20") (pinfunction "I/O1.7_20") (pintype "bidirectional"))
      (node (ref "LED701") (pin "A") (pinfunction "A_A") (pintype "passive"))
    )
    (net (code "158") (name "Net-(IC801-A_VREF)") (class "Default")
      (node (ref "IC801") (pin "12") (pinfunction "A_VREF_12") (pintype "input"))
      (node (ref "J801") (pin "2") (pinfunction "4_2") (pintype "passive"))
      (node (ref "R801") (pin "1") (pinfunction "1_1") (pintype "passive"))
      (node (ref "R801") (pin "2") (pinfunction "1_2") (pintype "passive"))
    )
    (net (code "159") (name "Net-(IC801-B_VREF)") (class "Default")
      (node (ref "IC801") (pin "13") (pinfunction "B_VREF_13") (pintype "input"))
      (node (ref "J801") (pin "4") (pinfunction "3_4") (pintype "passive"))
      (node (ref "R801") (pin "3") (pinfunction "1_3") (pintype "passive"))
      (node (ref "R801") (pin "4") (pinfunction "1_4") (pintype "passive"))
    )
    (net (code "160") (name "Net-(IC801-CP1)") (class "Default")
      (node (ref "C809") (pin "1") (pinfunction "1_1") (pintype "passive"))
      (node (ref "IC801") (pin "1") (pinfunction "CP1_1") (pintype "bidirectional"))
    )
    (net (code "161") (name "Net-(IC801-CP2)") (class "Default")
      (node (ref "C809") (pin "2") (pinfunction "2_2") (pintype "passive"))
      (node (ref "IC801") (pin "2") (pinfunction "CP2_2") (pintype "bidirectional"))
    )
    (net (code "162") (name "Net-(IC801-I_SENS_A)") (class "Default")
      (node (ref "IC801") (pin "6") (pinfunction "I_SENS_A_6") (pintype "output"))
      (node (ref "R803") (pin "1") (pinfunction "1_1") (pintype "passive"))
    )
    (net (code "163") (name "Net-(IC801-I_SENS_B)") (class "Default")
      (node (ref "IC801") (pin "9") (pinfunction "I_SENS_B_9") (pintype "output"))
      (node (ref "R804") (pin "1") (pinfunction "1_1") (pintype "passive"))
    )
    (net (code "164") (name "Net-(IC801-VCP)") (class "Default")
      (node (ref "C811") (pin "2") (pinfunction "2_2") (pintype "passive"))
      (node (ref "IC801") (pin "3") (pinfunction "VCP_3") (pintype "input"))
      (node (ref "R807") (pin "1") (pinfunction "1_1") (pintype "passive"))
    )
    (net (code "165") (name "Net-(IC802-A_VREF)") (class "Default")
      (node (ref "IC802") (pin "12") (pinfunction "A_VREF_12") (pintype "input"))
      (node (ref "J802") (pin "2") (pinfunction "4_2") (pintype "passive"))
      (node (ref "R802") (pin "1") (pinfunction "1_1") (pintype "passive"))
      (node (ref "R802") (pin "2") (pinfunction "1_2") (pintype "passive"))
    )
    (net (code "166") (name "Net-(IC802-B_VREF)") (class "Default")
      (node (ref "IC802") (pin "13") (pinfunction "B_VREF_13") (pintype "input"))
      (node (ref "J802") (pin "4") (pinfunction "3_4") (pintype "passive"))
      (node (ref "R802") (pin "3") (pinfunction "1_3") (pintype "passive"))
      (node (ref "R802") (pin "4") (pinfunction "1_4") (pintype "passive"))
    )
    (net (code "167") (name "Net-(IC802-CP1)") (class "Default")
      (node (ref "C810") (pin "1") (pinfunction "1_1") (pintype "passive"))
      (node (ref "IC802") (pin "1") (pinfunction "CP1_1") (pintype "bidirectional"))
    )
    (net (code "168") (name "Net-(IC802-CP2)") (class "Default")
      (node (ref "C810") (pin "2") (pinfunction "2_2") (pintype "passive"))
      (node (ref "IC802") (pin "2") (pinfunction "CP2_2") (pintype "bidirectional"))
    )
    (net (code "169") (name "Net-(IC802-I_SENS_A)") (class "Default")
      (node (ref "IC802") (pin "6") (pinfunction "I_SENS_A_6") (pintype "output"))
      (node (ref "R805") (pin "1") (pinfunction "1_1") (pintype "passive"))
    )
    (net (code "170") (name "Net-(IC802-I_SENS_B)") (class "Default")
      (node (ref "IC802") (pin "9") (pinfunction "I_SENS_B_9") (pintype "output"))
      (node (ref "R806") (pin "1") (pinfunction "1_1") (pintype "passive"))
    )
    (net (code "171") (name "Net-(IC802-VCP)") (class "Default")
      (node (ref "C812") (pin "2") (pinfunction "2_2") (pintype "passive"))
      (node (ref "IC802") (pin "3") (pinfunction "VCP_3") (pintype "input"))
      (node (ref "R808") (pin "1") (pinfunction "1_1") (pintype "passive"))
    )
    (net (code "172") (name "Net-(IC901-A_VREF)") (class "Default")
      (node (ref "IC901") (pin "12") (pinfunction "A_VREF_12") (pintype "input"))
      (node (ref "J901") (pin "2") (pinfunction "4_2") (pintype "passive"))
      (node (ref "R901") (pin "1") (pinfunction "1_1") (pintype "passive"))
      (node (ref "R901") (pin "2") (pinfunction "1_2") (pintype "passive"))
    )
    (net (code "173") (name "Net-(IC901-B_VREF)") (class "Default")
      (node (ref "IC901") (pin "13") (pinfunction "B_VREF_13") (pintype "input"))
      (node (ref "J901") (pin "4") (pinfunction "3_4") (pintype "passive"))
      (node (ref "R901") (pin "3") (pinfunction "1_3") (pintype "passive"))
      (node (ref "R901") (pin "4") (pinfunction "1_4") (pintype "passive"))
    )
    (net (code "174") (name "Net-(IC901-CP1)") (class "Default")
      (node (ref "C905") (pin "1") (pinfunction "1_1") (pintype "passive"))
      (node (ref "IC901") (pin "1") (pinfunction "CP1_1") (pintype "bidirectional"))
    )
    (net (code "175") (name "Net-(IC901-CP2)") (class "Default")
      (node (ref "C905") (pin "2") (pinfunction "2_2") (pintype "passive"))
      (node (ref "IC901") (pin "2") (pinfunction "CP2_2") (pintype "bidirectional"))
    )
    (net (code "176") (name "Net-(IC901-I_SENS_A)") (class "Default")
      (node (ref "IC901") (pin "6") (pinfunction "I_SENS_A_6") (pintype "output"))
      (node (ref "R902") (pin "1") (pinfunction "1_1") (pintype "passive"))
    )
    (net (code "177") (name "Net-(IC901-I_SENS_B)") (class "Default")
      (node (ref "IC901") (pin "9") (pinfunction "I_SENS_B_9") (pintype "output"))
      (node (ref "R903") (pin "1") (pinfunction "1_1") (pintype "passive"))
    )
    (net (code "178") (name "Net-(IC901-VCP)") (class "Default")
      (node (ref "C906") (pin "2") (pinfunction "2_2") (pintype "passive"))
      (node (ref "IC901") (pin "3") (pinfunction "VCP_3") (pintype "input"))
      (node (ref "R904") (pin "1") (pinfunction "1_1") (pintype "passive"))
    )
    (net (code "179") (name "Net-(J2-2)") (class "Default")
      (node (ref "J2") (pin "3") (pinfunction "2_3") (pintype "passive"))
      (node (ref "J601") (pin "3") (pinfunction "19_3") (pintype "passive"))
    )
    (net (code "180") (name "Net-(J2-3)") (class "Default")
      (node (ref "J2") (pin "5") (pinfunction "3_5") (pintype "passive"))
      (node (ref "J601") (pin "5") (pinfunction "18_5") (pintype "passive"))
    )
    (net (code "181") (name "Net-(J2-4)") (class "Default")
      (node (ref "J2") (pin "7") (pinfunction "4_7") (pintype "passive"))
      (node (ref "J601") (pin "7") (pinfunction "17_7") (pintype "passive"))
    )
    (net (code "182") (name "Net-(J2-6)") (class "Default")
      (node (ref "J2") (pin "11") (pinfunction "6_11") (pintype "passive"))
      (node (ref "J601") (pin "11") (pinfunction "15_11") (pintype "passive"))
    )
    (net (code "183") (name "Net-(J2-7)") (class "Default")
      (node (ref "J2") (pin "13") (pinfunction "7_13") (pintype "passive"))
      (node (ref "J601") (pin "13") (pinfunction "14_13") (pintype "passive"))
    )
    (net (code "184") (name "Net-(J2-8)") (class "Default")
      (node (ref "J2") (pin "15") (pinfunction "8_15") (pintype "passive"))
      (node (ref "J601") (pin "15") (pinfunction "13_15") (pintype "passive"))
    )
    (net (code "185") (name "Net-(J2-9)") (class "Default")
      (node (ref "J2") (pin "17") (pinfunction "9_17") (pintype "passive"))
      (node (ref "J601") (pin "17") (pinfunction "12_17") (pintype "passive"))
    )
    (net (code "186") (name "Net-(J2-10)") (class "Default")
      (node (ref "J2") (pin "19") (pinfunction "10_19") (pintype "passive"))
      (node (ref "J601") (pin "19") (pinfunction "11_19") (pintype "passive"))
    )
    (net (code "187") (name "Net-(J2-12)") (class "Default")
      (node (ref "J2") (pin "18") (pinfunction "12_18") (pintype "passive"))
      (node (ref "J601") (pin "18") (pinfunction "9_18") (pintype "passive"))
    )
    (net (code "188") (name "Net-(J2-13)") (class "Default")
      (node (ref "J2") (pin "16") (pinfunction "13_16") (pintype "passive"))
      (node (ref "J601") (pin "16") (pinfunction "8_16") (pintype "passive"))
    )
    (net (code "189") (name "Net-(J2-15)") (class "Default")
      (node (ref "J2") (pin "12") (pinfunction "15_12") (pintype "passive"))
      (node (ref "J601") (pin "12") (pinfunction "6_12") (pintype "passive"))
    )
    (net (code "190") (name "Net-(J3-2)") (class "Default")
      (node (ref "J3") (pin "3") (pinfunction "2_3") (pintype "passive"))
      (node (ref "J602") (pin "3") (pinfunction "19_3") (pintype "passive"))
    )
    (net (code "191") (name "Net-(J3-4)") (class "Default")
      (node (ref "J3") (pin "7") (pinfunction "4_7") (pintype "passive"))
      (node (ref "J602") (pin "7") (pinfunction "17_7") (pintype "passive"))
    )
    (net (code "192") (name "Net-(J3-5)") (class "Default")
      (node (ref "J3") (pin "9") (pinfunction "5_9") (pintype "passive"))
      (node (ref "J602") (pin "9") (pinfunction "16_9") (pintype "passive"))
    )
    (net (code "193") (name "Net-(J3-6)") (class "Default")
      (node (ref "J3") (pin "11") (pinfunction "6_11") (pintype "passive"))
      (node (ref "J602") (pin "11") (pinfunction "15_11") (pintype "passive"))
    )
    (net (code "194") (name "Net-(J3-7)") (class "Default")
      (node (ref "J3") (pin "13") (pinfunction "7_13") (pintype "passive"))
      (node (ref "J602") (pin "13") (pinfunction "14_13") (pintype "passive"))
    )
    (net (code "195") (name "Net-(J3-8)") (class "Default")
      (node (ref "J3") (pin "15") (pinfunction "8_15") (pintype "passive"))
      (node (ref "J602") (pin "15") (pinfunction "13_15") (pintype "passive"))
    )
    (net (code "196") (name "Net-(J3-9)") (class "Default")
      (node (ref "J3") (pin "17") (pinfunction "9_17") (pintype "passive"))
      (node (ref "J602") (pin "17") (pinfunction "12_17") (pintype "passive"))
    )
    (net (code "197") (name "Net-(J3-11)") (class "Default")
      (node (ref "J3") (pin "20") (pinfunction "11_20") (pintype "passive"))
      (node (ref "J602") (pin "20") (pinfunction "10_20") (pintype "passive"))
    )
    (net (code "198") (name "Net-(J3-12)") (class "Default")
      (node (ref "J3") (pin "18") (pinfunction "12_18") (pintype "passive"))
      (node (ref "J602") (pin "18") (pinfunction "9_18") (pintype "passive"))
    )
    (net (code "199") (name "Net-(J3-13)") (class "Default")
      (node (ref "J3") (pin "16") (pinfunction "13_16") (pintype "passive"))
      (node (ref "J602") (pin "16") (pinfunction "8_16") (pintype "passive"))
    )
    (net (code "200") (name "Net-(J3-15)") (class "Default")
      (node (ref "J3") (pin "12") (pinfunction "15_12") (pintype "passive"))
      (node (ref "J602") (pin "12") (pinfunction "6_12") (pintype "passive"))
    )
    (net (code "201") (name "Net-(J3-17)") (class "Default")
      (node (ref "J3") (pin "8") (pinfunction "17_8") (pintype "passive"))
      (node (ref "J602") (pin "8") (pinfunction "4_8") (pintype "passive"))
    )
    (net (code "202") (name "Net-(J3-18)") (class "Default")
      (node (ref "J3") (pin "6") (pinfunction "18_6") (pintype "passive"))
      (node (ref "J602") (pin "6") (pinfunction "3_6") (pintype "passive"))
    )
    (net (code "203") (name "Net-(J3-19)") (class "Default")
      (node (ref "J3") (pin "4") (pinfunction "19_4") (pintype "passive"))
      (node (ref "J602") (pin "4") (pinfunction "2_4") (pintype "passive"))
    )
    (net (code "204") (name "Net-(J3-20)") (class "Default")
      (node (ref "J3") (pin "2") (pinfunction "20_2") (pintype "passive"))
      (node (ref "J602") (pin "2") (pinfunction "1_2") (pintype "passive"))
    )
    (net (code "205") (name "Net-(J601-20)") (class "Default")
      (node (ref "J2") (pin "1") (pinfunction "1_1") (pintype "passive"))
      (node (ref "J601") (pin "1") (pinfunction "20_1") (pintype "passive"))
    )
    (net (code "206") (name "Net-(J602-20)") (class "Default")
      (node (ref "J3") (pin "1") (pinfunction "1_1") (pintype "passive"))
      (node (ref "J602") (pin "1") (pinfunction "20_1") (pintype "passive"))
    )
    (net (code "207") (name "Net-(R1B-1)") (class "Default")
      (node (ref "R1") (pin "2") (pinfunction "1_2") (pintype "passive"))
      (node (ref "R1") (pin "6") (pinfunction "2_6") (pintype "passive"))
    )
    (net (code "208") (name "Net-(R2B-2)") (class "Default")
      (node (ref "R2") (pin "3") (pinfunction "1_3") (pintype "passive"))
      (node (ref "R2") (pin "7") (pinfunction "2_7") (pintype "passive"))
    )
    (net (code "209") (name "Net-(R701A-2)") (class "Default")
      (node (ref "LED704") (pin "C") (pinfunction "C_C") (pintype "passive"))
      (node (ref "R701") (pin "8") (pinfunction "2_8") (pintype "passive"))
    )
    (net (code "210") (name "Net-(R701B-2)") (class "Default")
      (node (ref "LED703") (pin "C") (pinfunction "C_C") (pintype "passive"))
      (node (ref "R701") (pin "7") (pinfunction "2_7") (pintype "passive"))
    )
    (net (code "211") (name "Net-(R701C-2)") (class "Default")
      (node (ref "LED702") (pin "C") (pinfunction "C_C") (pintype "passive"))
      (node (ref "R701") (pin "6") (pinfunction "2_6") (pintype "passive"))
    )
    (net (code "212") (name "Net-(R701D-2)") (class "Default")
      (node (ref "LED701") (pin "C") (pinfunction "C_C") (pintype "passive"))
      (node (ref "R701") (pin "5") (pinfunction "2_5") (pintype "passive"))
    )
    (net (code "213") (name "Net-(R702A-2)") (class "Default")
      (node (ref "LED708") (pin "C") (pinfunction "C_C") (pintype "passive"))
      (node (ref "R702") (pin "8") (pinfunction "2_8") (pintype "passive"))
    )
    (net (code "214") (name "Net-(R702B-2)") (class "Default")
      (node (ref "LED707") (pin "C") (pinfunction "C_C") (pintype "passive"))
      (node (ref "R702") (pin "7") (pinfunction "2_7") (pintype "passive"))
    )
    (net (code "215") (name "Net-(R702C-2)") (class "Default")
      (node (ref "LED706") (pin "C") (pinfunction "C_C") (pintype "passive"))
      (node (ref "R702") (pin "6") (pinfunction "2_6") (pintype "passive"))
    )
    (net (code "216") (name "Net-(R702D-2)") (class "Default")
      (node (ref "LED705") (pin "C") (pinfunction "C_C") (pintype "passive"))
      (node (ref "R702") (pin "5") (pinfunction "2_5") (pintype "passive"))
    )
    (net (code "217") (name "Net-(U101-2RON)") (class "Default")
      (node (ref "R102") (pin "1") (pinfunction "1_1") (pintype "passive"))
      (node (ref "U101") (pin "2") (pinfunction "2RON_2") (pintype "bidirectional"))
    )
    (net (code "218") (name "Net-(U101-3EN)") (class "Default")
      (node (ref "C101") (pin "2") (pinfunction "2_2") (pintype "passive"))
      (node (ref "U101") (pin "3") (pinfunction "3EN_3") (pintype "bidirectional"))
    )
    (net (code "219") (name "Net-(U101-5SS)") (class "Default")
      (node (ref "C103") (pin "1") (pinfunction "1_1") (pintype "passive"))
      (node (ref "U101") (pin "5") (pinfunction "5SS_5") (pintype "bidirectional"))
    )
    (net (code "220") (name "Net-(U101-6FB)") (class "Default")
      (node (ref "C102") (pin "2") (pinfunction "2_2") (pintype "passive"))
      (node (ref "R101") (pin "2") (pinfunction "2_2") (pintype "passive"))
      (node (ref "R103") (pin "2") (pinfunction "2_2") (pintype "passive"))
      (node (ref "U101") (pin "6") (pinfunction "6FB_6") (pintype "bidirectional"))
    )
    (net (code "221") (name "RXDUART") (class "Default")
      (node (ref "J1") (pin "10") (pinfunction "16_10") (pintype "passive"))
      (node (ref "J501") (pin "10") (pinfunction "5_10") (pintype "passive"))
      (node (ref "R6") (pin "1") (pinfunction "1_1") (pintype "passive"))
    )
    (net (code "222") (name "RXPI2") (class "Default")
      (node (ref "J2") (pin "10") (pinfunction "16_10") (pintype "passive"))
      (node (ref "J601") (pin "10") (pinfunction "5_10") (pintype "passive"))
      (node (ref "R4") (pin "2") (pinfunction "2_2") (pintype "passive"))
    )
    (net (code "223") (name "SCL") (class "Default")
      (node (ref "IC401") (pin "23") (pinfunction "SCL_23") (pintype "bidirectional"))
      (node (ref "IC701") (pin "22") (pinfunction "SCL_22") (pintype "input"))
      (node (ref "IC702") (pin "22") (pinfunction "SCL_22") (pintype "input"))
      (node (ref "J1") (pin "5") (pinfunction "3_5") (pintype "passive"))
      (node (ref "J501") (pin "5") (pinfunction "18_5") (pintype "passive"))
      (node (ref "R401") (pin "1") (pinfunction "1_1") (pintype "passive"))
    )
    (net (code "224") (name "SDA") (class "Default")
      (node (ref "IC401") (pin "24") (pinfunction "SDA_24") (pintype "bidirectional"))
      (node (ref "IC701") (pin "23") (pinfunction "SDA_23") (pintype "bidirectional"))
      (node (ref "IC702") (pin "23") (pinfunction "SDA_23") (pintype "bidirectional"))
      (node (ref "J1") (pin "3") (pinfunction "2_3") (pintype "passive"))
      (node (ref "J501") (pin "3") (pinfunction "19_3") (pintype "passive"))
      (node (ref "R402") (pin "1") (pinfunction "1_1") (pintype "passive"))
    )
    (net (code "225") (name "SENSOR_IN0") (class "Default")
      (node (ref "IC301") (pin "13") (pinfunction "B1_13") (pintype "input"))
      (node (ref "J201") (pin "3") (pinfunction "2_3") (pintype "passive"))
    )
    (net (code "226") (name "SENSOR_IN1") (class "Default")
      (node (ref "IC301") (pin "14") (pinfunction "B2_14") (pintype "input"))
      (node (ref "J203") (pin "3") (pinfunction "2_3") (pintype "passive"))
    )
    (net (code "227") (name "SENSOR_IN2") (class "Default")
      (node (ref "IC301") (pin "15") (pinfunction "B3_15") (pintype "input"))
      (node (ref "J205") (pin "3") (pinfunction "2_3") (pintype "passive"))
    )
    (net (code "228") (name "SENSOR_IN3") (class "Default")
      (node (ref "IC301") (pin "12") (pinfunction "B4_12") (pintype "input"))
      (node (ref "J207") (pin "3") (pinfunction "2_3") (pintype "passive"))
    )
    (net (code "229") (name "SENSOR_IN4") (class "Default")
      (node (ref "IC301") (pin "1") (pinfunction "B5_1") (pintype "input"))
      (node (ref "J209") (pin "3") (pinfunction "2_3") (pintype "passive"))
    )
    (net (code "230") (name "SENSOR_IN5") (class "Default")
      (node (ref "IC301") (pin "5") (pinfunction "B6_5") (pintype "input"))
      (node (ref "J211") (pin "3") (pinfunction "2_3") (pintype "passive"))
    )
    (net (code "231") (name "SENSOR_IN6") (class "Default")
      (node (ref "IC301") (pin "2") (pinfunction "B7_2") (pintype "input"))
      (node (ref "J213") (pin "3") (pinfunction "2_3") (pintype "passive"))
    )
    (net (code "232") (name "SENSOR_IN7") (class "Default")
      (node (ref "IC301") (pin "4") (pinfunction "B8_4") (pintype "input"))
      (node (ref "J215") (pin "3") (pinfunction "2_3") (pintype "passive"))
    )
    (net (code "233") (name "SENSOR_IN8") (class "Default")
      (node (ref "IC303") (pin "13") (pinfunction "B1_13") (pintype "input"))
      (node (ref "J216") (pin "3") (pinfunction "2_3") (pintype "passive"))
    )
    (net (code "234") (name "SENSOR_IN9") (class "Default")
      (node (ref "IC303") (pin "14") (pinfunction "B2_14") (pintype "input"))
      (node (ref "J214") (pin "3") (pinfunction "2_3") (pintype "passive"))
    )
    (net (code "235") (name "SENSOR_IN10") (class "Default")
      (node (ref "IC303") (pin "15") (pinfunction "B3_15") (pintype "input"))
      (node (ref "J212") (pin "3") (pinfunction "2_3") (pintype "passive"))
    )
    (net (code "236") (name "SENSOR_IN11") (class "Default")
      (node (ref "IC303") (pin "12") (pinfunction "B4_12") (pintype "input"))
      (node (ref "J210") (pin "3") (pinfunction "2_3") (pintype "passive"))
    )
    (net (code "237") (name "SENSOR_IN12") (class "Default")
      (node (ref "IC303") (pin "1") (pinfunction "B5_1") (pintype "input"))
      (node (ref "J208") (pin "3") (pinfunction "2_3") (pintype "passive"))
    )
    (net (code "238") (name "SENSOR_IN13") (class "Default")
      (node (ref "IC303") (pin "5") (pinfunction "B6_5") (pintype "input"))
      (node (ref "J206") (pin "3") (pinfunction "2_3") (pintype "passive"))
    )
    (net (code "239") (name "SENSOR_IN14") (class "Default")
      (node (ref "IC303") (pin "2") (pinfunction "B7_2") (pintype "input"))
      (node (ref "J204") (pin "3") (pinfunction "2_3") (pintype "passive"))
    )
    (net (code "240") (name "SENSOR_IN15") (class "Default")
      (node (ref "IC303") (pin "4") (pinfunction "B8_4") (pintype "input"))
      (node (ref "J202") (pin "3") (pinfunction "2_3") (pintype "passive"))
    )
    (net (code "241") (name "SENSOR_OUT0") (class "Default")
      (node (ref "IC302") (pin "13") (pinfunction "B1_13") (pintype "input"))
      (node (ref "J201") (pin "2") (pinfunction "3_2") (pintype "passive"))
    )
    (net (code "242") (name "SENSOR_OUT1") (class "Default")
      (node (ref "IC302") (pin "14") (pinfunction "B2_14") (pintype "input"))
      (node (ref "J203") (pin "2") (pinfunction "3_2") (pintype "passive"))
    )
    (net (code "243") (name "SENSOR_OUT2") (class "Default")
      (node (ref "IC302") (pin "15") (pinfunction "B3_15") (pintype "input"))
      (node (ref "J205") (pin "2") (pinfunction "3_2") (pintype "passive"))
    )
    (net (code "244") (name "SENSOR_OUT3") (class "Default")
      (node (ref "IC302") (pin "12") (pinfunction "B4_12") (pintype "input"))
      (node (ref "J207") (pin "2") (pinfunction "3_2") (pintype "passive"))
    )
    (net (code "245") (name "SENSOR_OUT4") (class "Default")
      (node (ref "IC302") (pin "1") (pinfunction "B5_1") (pintype "input"))
      (node (ref "J209") (pin "2") (pinfunction "3_2") (pintype "passive"))
    )
    (net (code "246") (name "SENSOR_OUT5") (class "Default")
      (node (ref "IC302") (pin "5") (pinfunction "B6_5") (pintype "input"))
      (node (ref "J211") (pin "2") (pinfunction "3_2") (pintype "passive"))
    )
    (net (code "247") (name "SENSOR_OUT6") (class "Default")
      (node (ref "IC302") (pin "2") (pinfunction "B7_2") (pintype "input"))
      (node (ref "J213") (pin "2") (pinfunction "3_2") (pintype "passive"))
    )
    (net (code "248") (name "SENSOR_OUT7") (class "Default")
      (node (ref "IC302") (pin "4") (pinfunction "B8_4") (pintype "input"))
      (node (ref "J215") (pin "2") (pinfunction "3_2") (pintype "passive"))
    )
    (net (code "249") (name "SENSOR_OUT8") (class "Default")
      (node (ref "IC304") (pin "13") (pinfunction "B1_13") (pintype "input"))
      (node (ref "J216") (pin "2") (pinfunction "3_2") (pintype "passive"))
    )
    (net (code "250") (name "SENSOR_OUT9") (class "Default")
      (node (ref "IC304") (pin "14") (pinfunction "B2_14") (pintype "input"))
      (node (ref "J214") (pin "2") (pinfunction "3_2") (pintype "passive"))
    )
    (net (code "251") (name "SENSOR_OUT10") (class "Default")
      (node (ref "IC304") (pin "15") (pinfunction "B3_15") (pintype "input"))
      (node (ref "J212") (pin "2") (pinfunction "3_2") (pintype "passive"))
    )
    (net (code "252") (name "SENSOR_OUT11") (class "Default")
      (node (ref "IC304") (pin "12") (pinfunction "B4_12") (pintype "input"))
      (node (ref "J210") (pin "2") (pinfunction "3_2") (pintype "passive"))
    )
    (net (code "253") (name "SENSOR_OUT12") (class "Default")
      (node (ref "IC304") (pin "1") (pinfunction "B5_1") (pintype "input"))
      (node (ref "J208") (pin "2") (pinfunction "3_2") (pintype "passive"))
    )
    (net (code "254") (name "SENSOR_OUT13") (class "Default")
      (node (ref "IC304") (pin "5") (pinfunction "B6_5") (pintype "input"))
      (node (ref "J206") (pin "2") (pinfunction "3_2") (pintype "passive"))
    )
    (net (code "255") (name "SENSOR_OUT14") (class "Default")
      (node (ref "IC304") (pin "2") (pinfunction "B7_2") (pintype "input"))
      (node (ref "J204") (pin "2") (pinfunction "3_2") (pintype "passive"))
    )
    (net (code "256") (name "SENSOR_OUT15") (class "Default")
      (node (ref "IC304") (pin "4") (pinfunction "B8_4") (pintype "input"))
      (node (ref "J202") (pin "2") (pinfunction "3_2") (pintype "passive"))
    )
    (net (code "257") (name "TXDUART") (class "Default")
      (node (ref "J1") (pin "8") (pinfunction "17_8") (pintype "passive"))
      (node (ref "J501") (pin "8") (pinfunction "4_8") (pintype "passive"))
      (node (ref "R4") (pin "1") (pinfunction "1_1") (pintype "passive"))
    )
    (net (code "258") (name "TXPI2") (class "Default")
      (node (ref "J2") (pin "8") (pinfunction "17_8") (pintype "passive"))
      (node (ref "J601") (pin "8") (pinfunction "4_8") (pintype "passive"))
      (node (ref "R6") (pin "2") (pinfunction "2_2") (pintype "passive"))
    )
    (net (code "259") (name "VIO") (class "Default")
      (node (ref "C404") (pin "1") (pinfunction "1_1") (pintype "passive"))
      (node (ref "IC401") (pin "8") (pinfunction "VLOGIC_8") (pintype "bidirectional"))
    )
    (net (code "260") (name "unconnected-(IC701-~{INT}-Pad1)") (class "Default")
      (node (ref "IC701") (pin "1") (pinfunction "~{INT}_1") (pintype "output"))
    )
    (net (code "261") (name "unconnected-(IC702-~{INT}-Pad1)") (class "Default")
      (node (ref "IC702") (pin "1") (pinfunction "~{INT}_1") (pintype "output"))
    )
    (net (code "262") (name "unconnected-(IC704C-O-Pad8)") (class "Default")
      (node (ref "IC704") (pin "8") (pinfunction "O_8") (pintype "output"))
    )
    (net (code "263") (name "unconnected-(IC704D-O-Pad11)") (class "Default")
      (node (ref "IC704") (pin "11") (pinfunction "O_11") (pintype "output"))
    )
    (net (code "264") (name "unconnected-(IC801-~{FAULT}-Pad18)") (class "Default")
      (node (ref "IC801") (pin "18") (pinfunction "~{FAULT}_18") (pintype "open_collector"))
    )
    (net (code "265") (name "unconnected-(IC802-~{FAULT}-Pad18)") (class "Default")
      (node (ref "IC802") (pin "18") (pinfunction "~{FAULT}_18") (pintype "open_collector"))
    )
    (net (code "266") (name "unconnected-(IC901-~{FAULT}-Pad18)") (class "Default")
      (node (ref "IC901") (pin "18") (pinfunction "~{FAULT}_18") (pintype "open_collector"))
    )
    (net (code "267") (name "unconnected-(J4-4-Pad7)") (class "Default")
      (node (ref "J4") (pin "7") (pinfunction "4_7") (pintype "passive"))
    )
    (net (code "268") (name "unconnected-(J4-17-Pad8)") (class "Default")
      (node (ref "J4") (pin "8") (pinfunction "17_8") (pintype "passive"))
    )
    (net (code "269") (name "unconnected-(J502-4-Pad8)") (class "Default")
      (node (ref "J502") (pin "8") (pinfunction "4_8") (pintype "passive"))
    )
    (net (code "270") (name "unconnected-(J502-17-Pad7)") (class "Default")
      (node (ref "J502") (pin "7") (pinfunction "17_7") (pintype "passive"))
    )
    (net (code "271") (name "unconnected-(J701-3-Pad6)") (class "Default")
      (node (ref "J701") (pin "6") (pinfunction "3_6") (pintype "passive"))
    )
    (net (code "272") (name "unconnected-(J701-6-Pad3)") (class "Default")
      (node (ref "J701") (pin "3") (pinfunction "6_3") (pintype "passive"))
    )
    (net (code "273") (name "unconnected-(J702-3-Pad6)") (class "Default")
      (node (ref "J702") (pin "6") (pinfunction "3_6") (pintype "passive"))
    )
    (net (code "274") (name "unconnected-(J702-6-Pad3)") (class "Default")
      (node (ref "J702") (pin "3") (pinfunction "6_3") (pintype "passive"))
    )
    (net (code "275") (name "unconnected-(R8-Pad1)") (class "Default")
      (node (ref "R8") (pin "1") (pinfunction "1_1") (pintype "passive"))
    )
    (net (code "276") (name "unconnected-(R8B-1-Pad2)") (class "Default")
      (node (ref "R8") (pin "2") (pinfunction "1_2") (pintype "passive"))
    )
    (net (code "277") (name "unconnected-(S2-3-Pad2)") (class "Default")
      (node (ref "S2") (pin "2") (pinfunction "3_2") (pintype "passive"))
    )
    (net (code "278") (name "unconnected-(S3-3-Pad2)") (class "Default")
      (node (ref "S3") (pin "2") (pinfunction "3_2") (pintype "passive"))
    )
  )
)
